# Ranger_PCB.net
KiCad netlist of a schematic drawn in EasyEDA
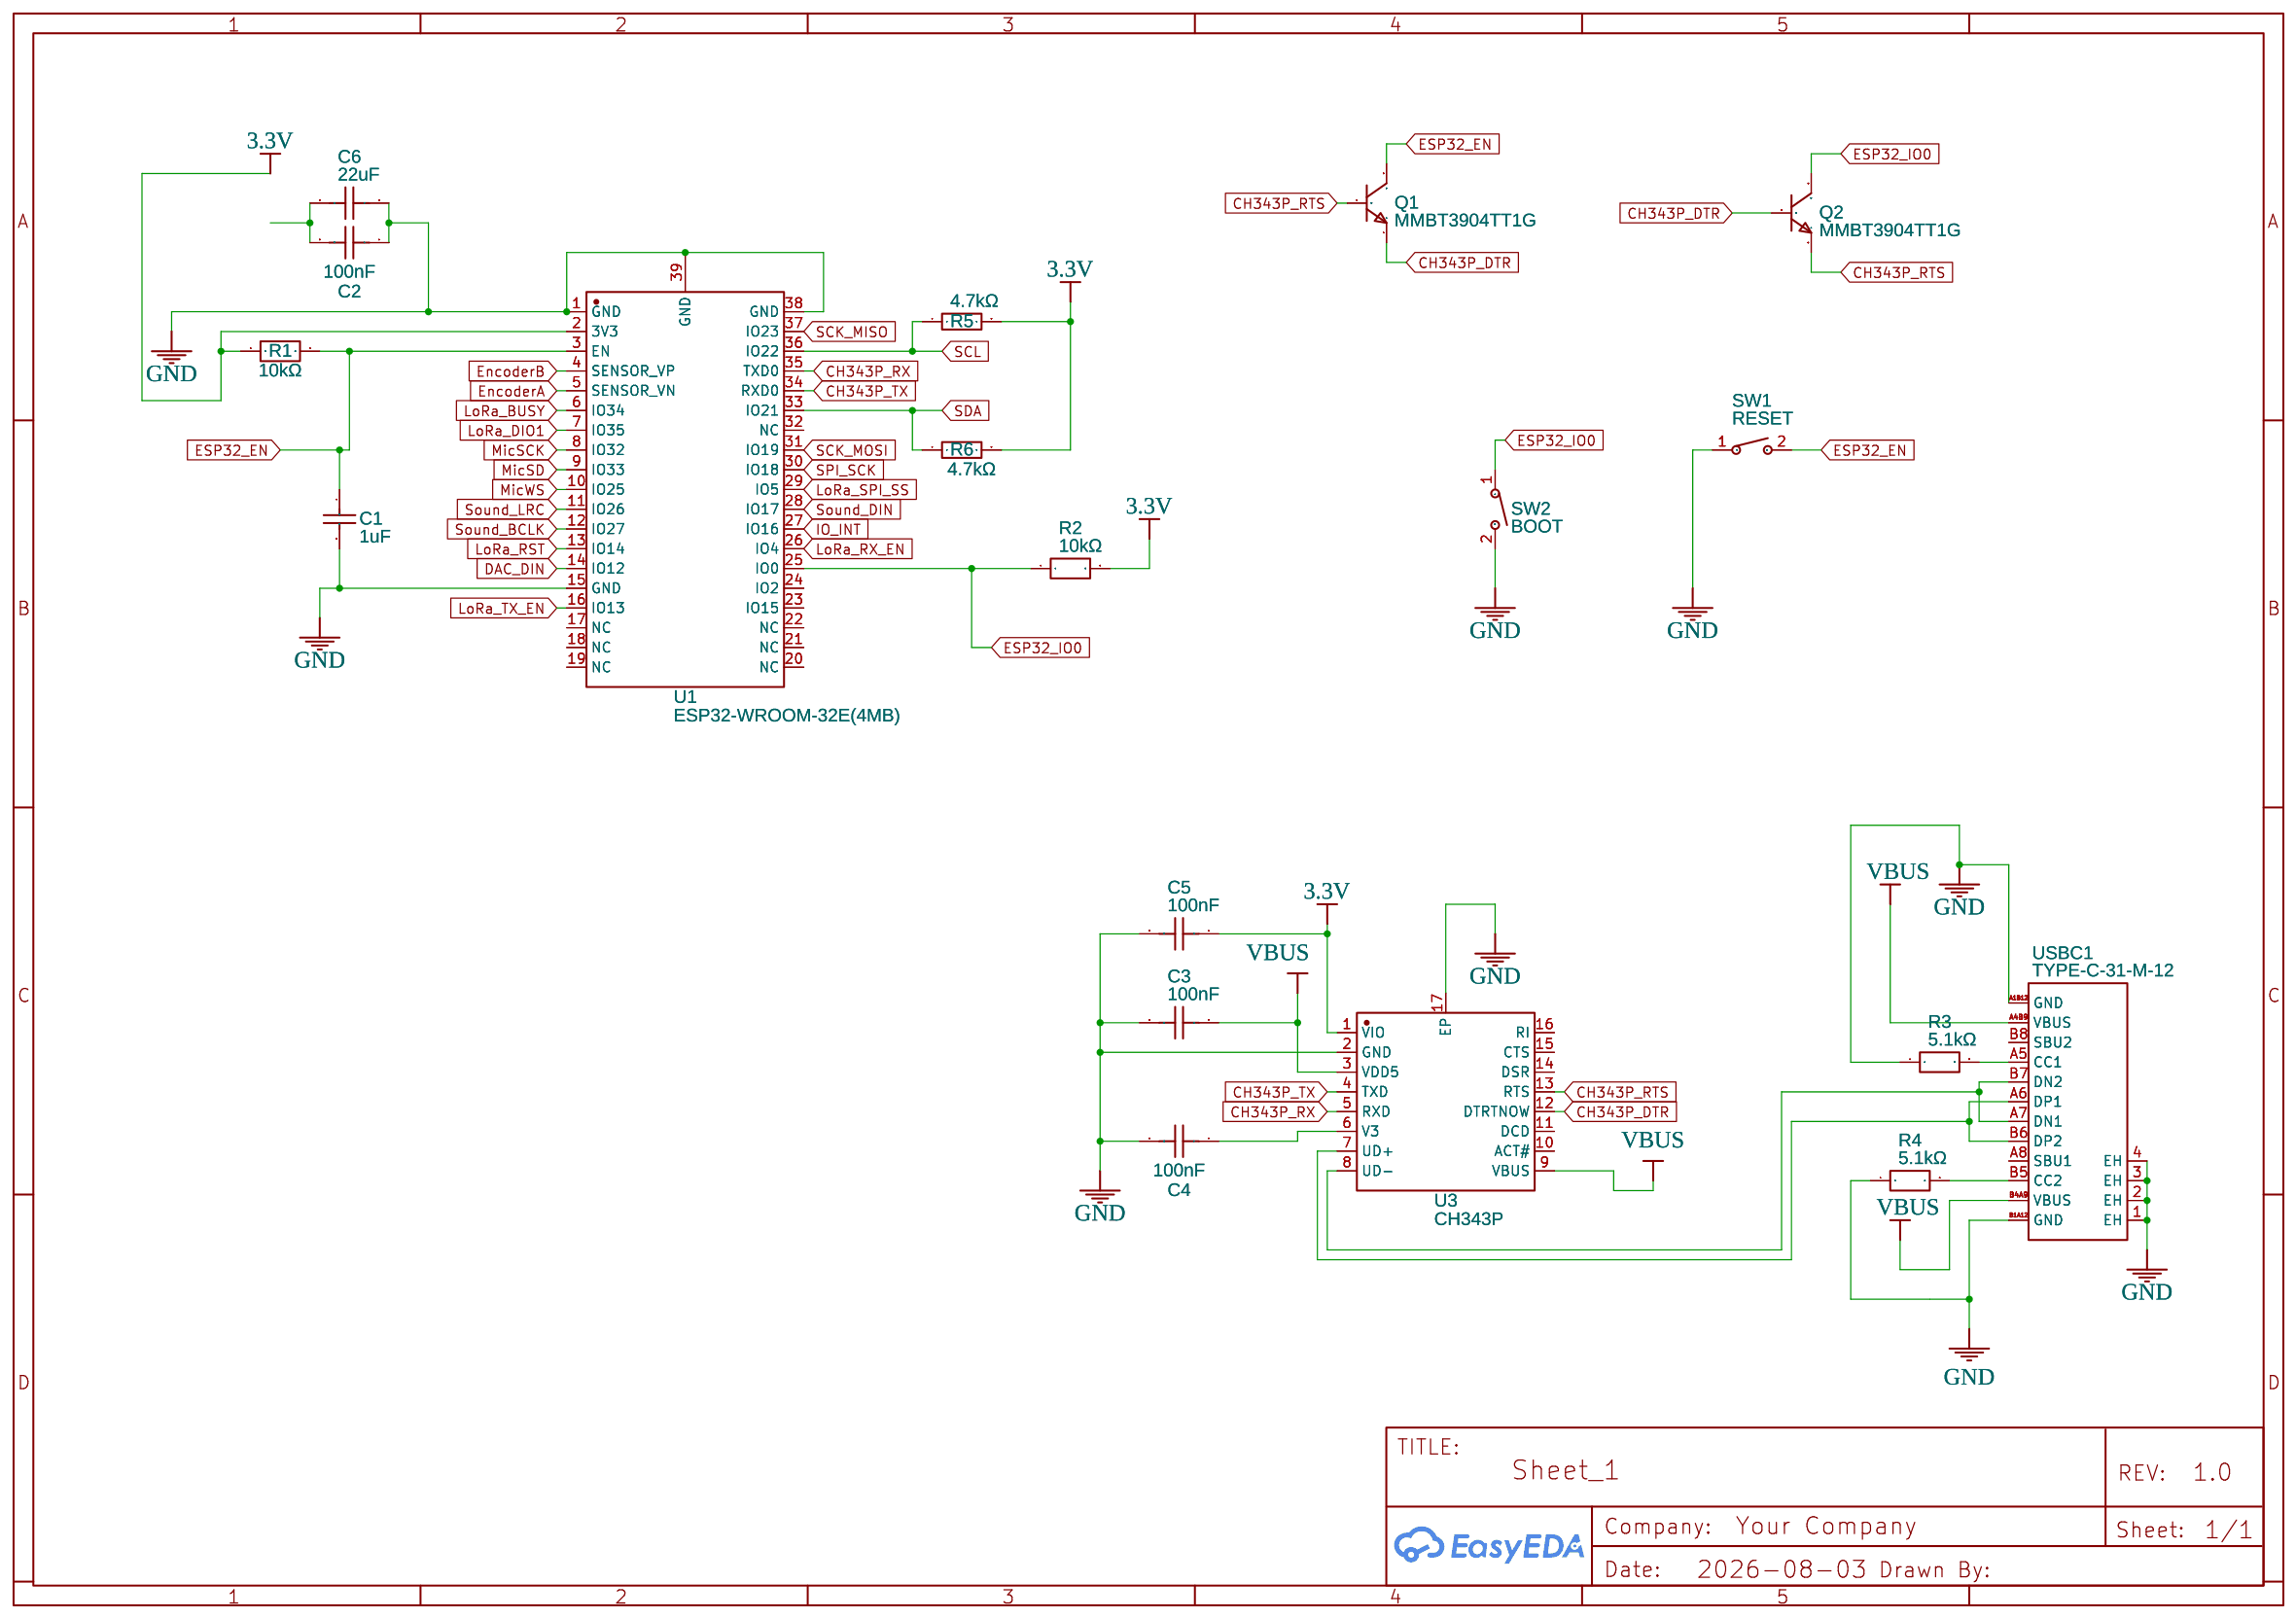
[diagram p0: ESP32]
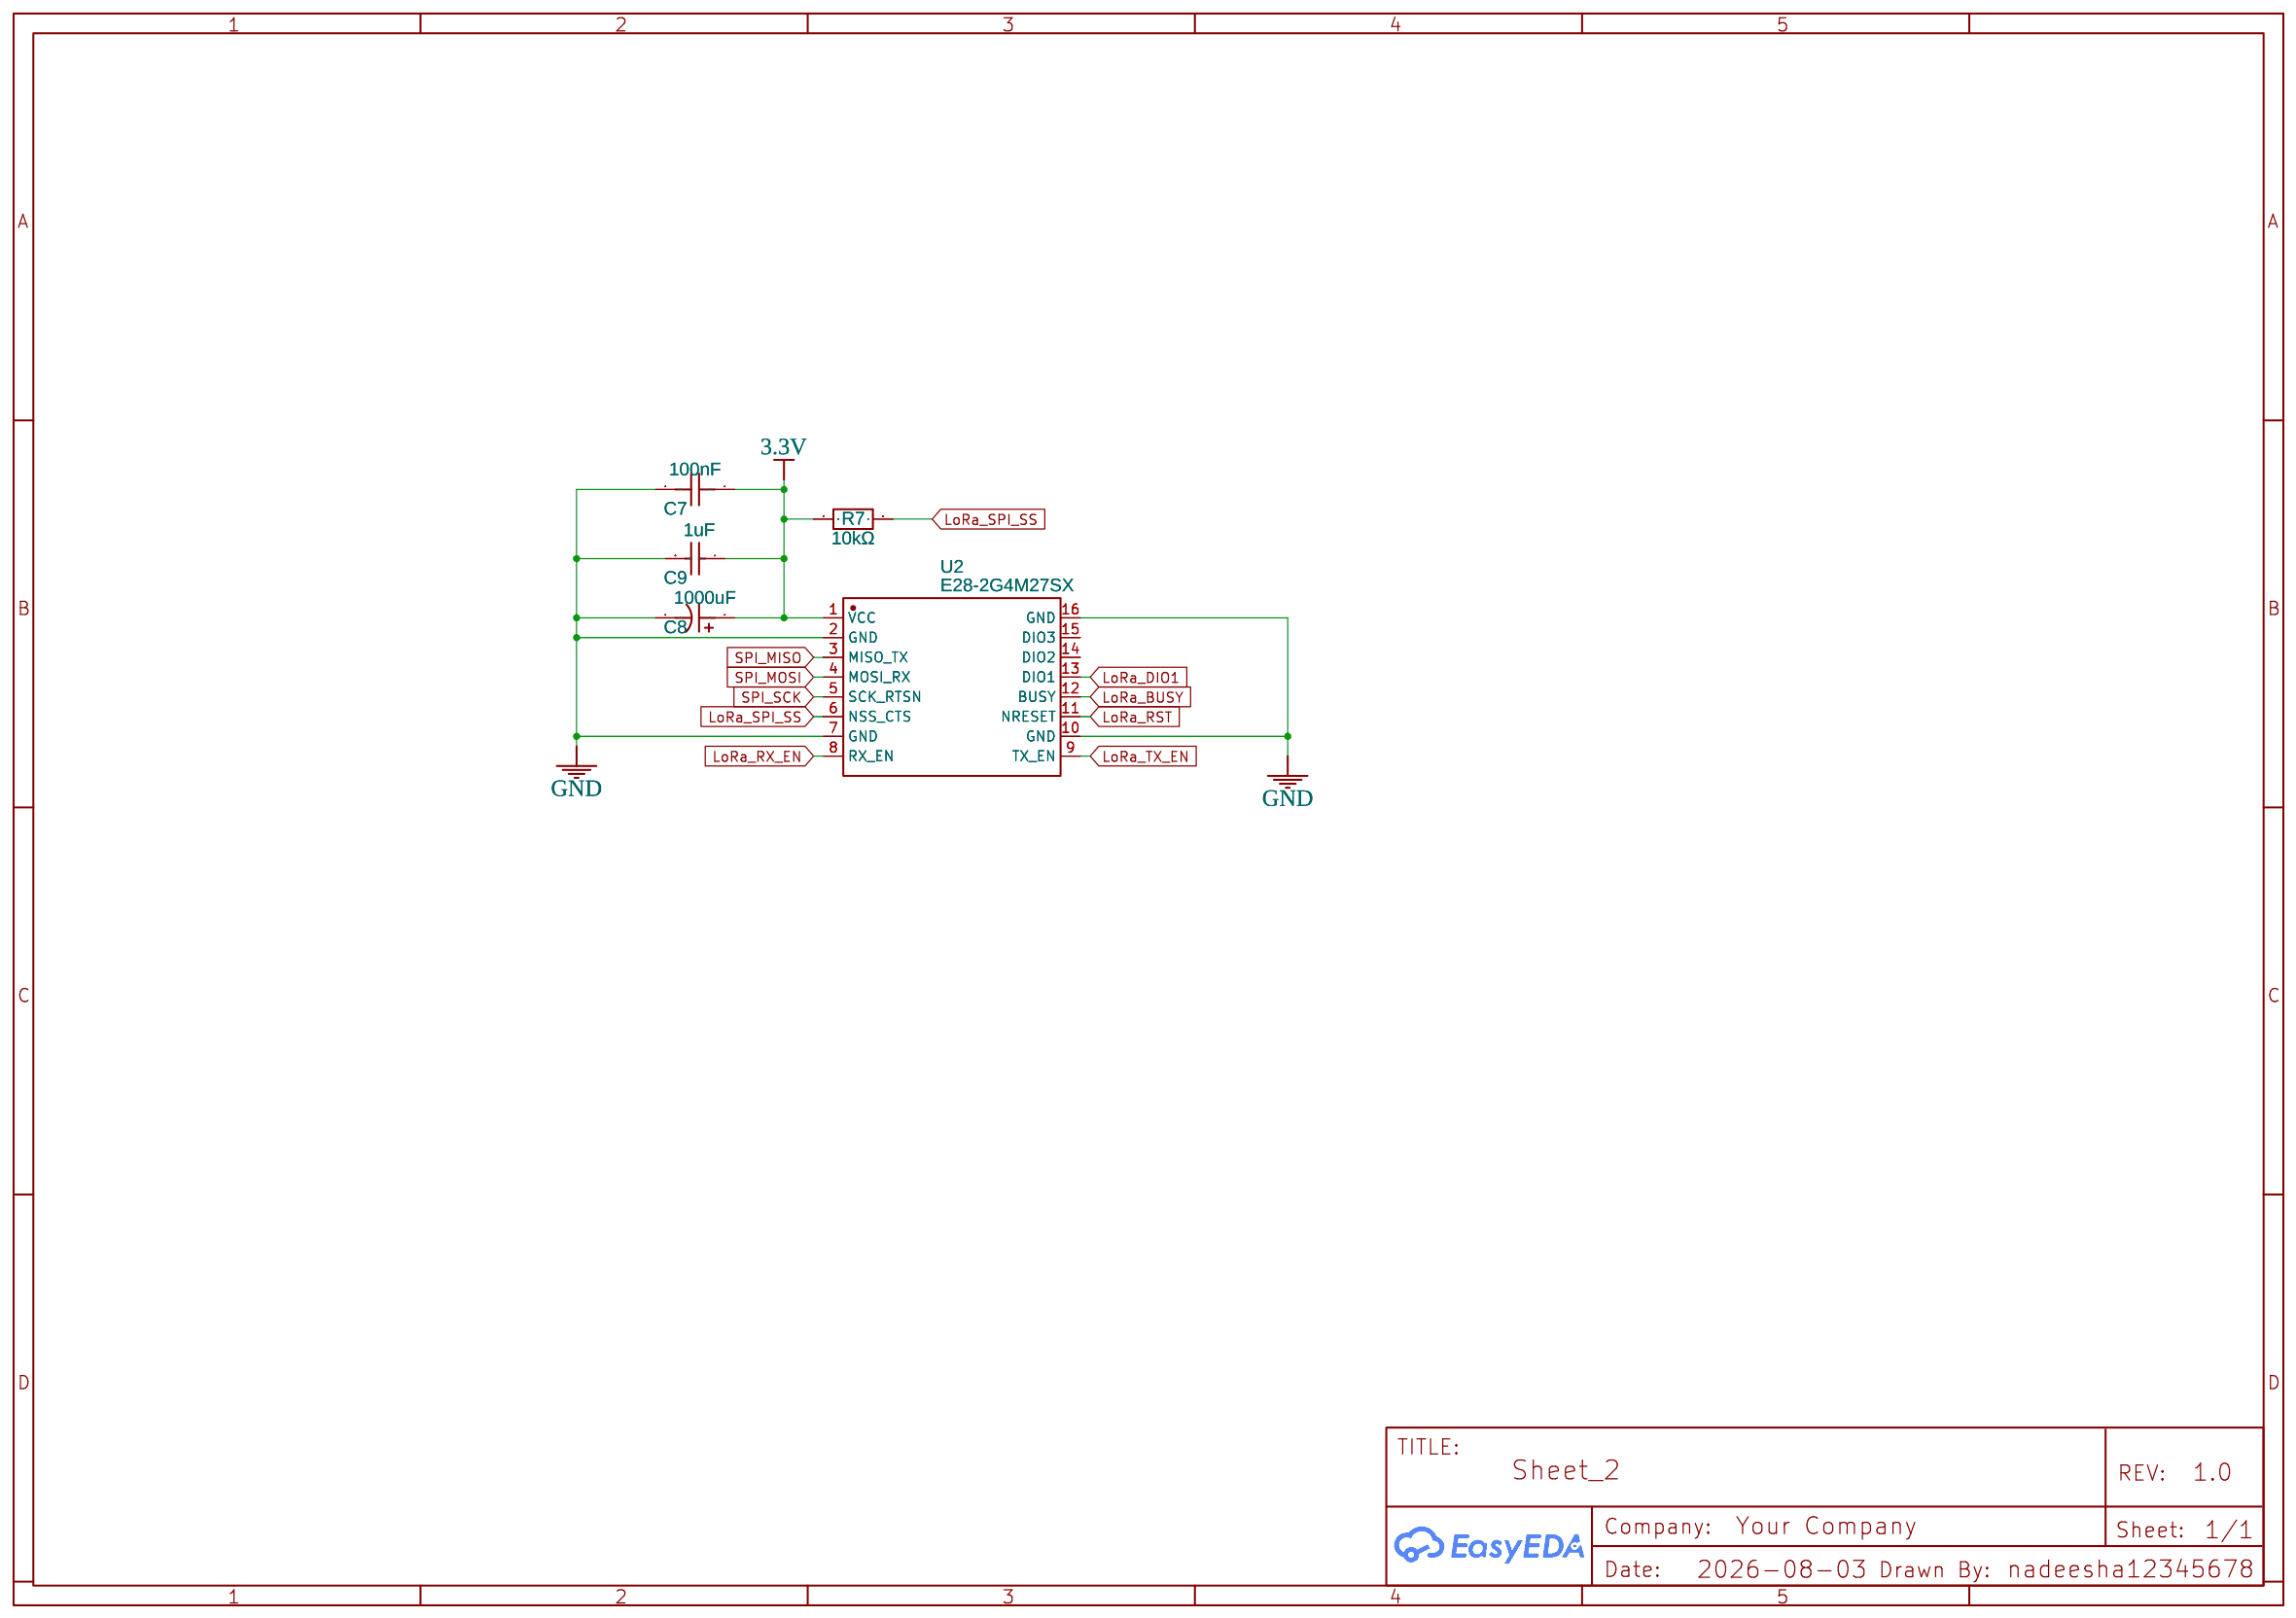
[diagram p1: LoRa]
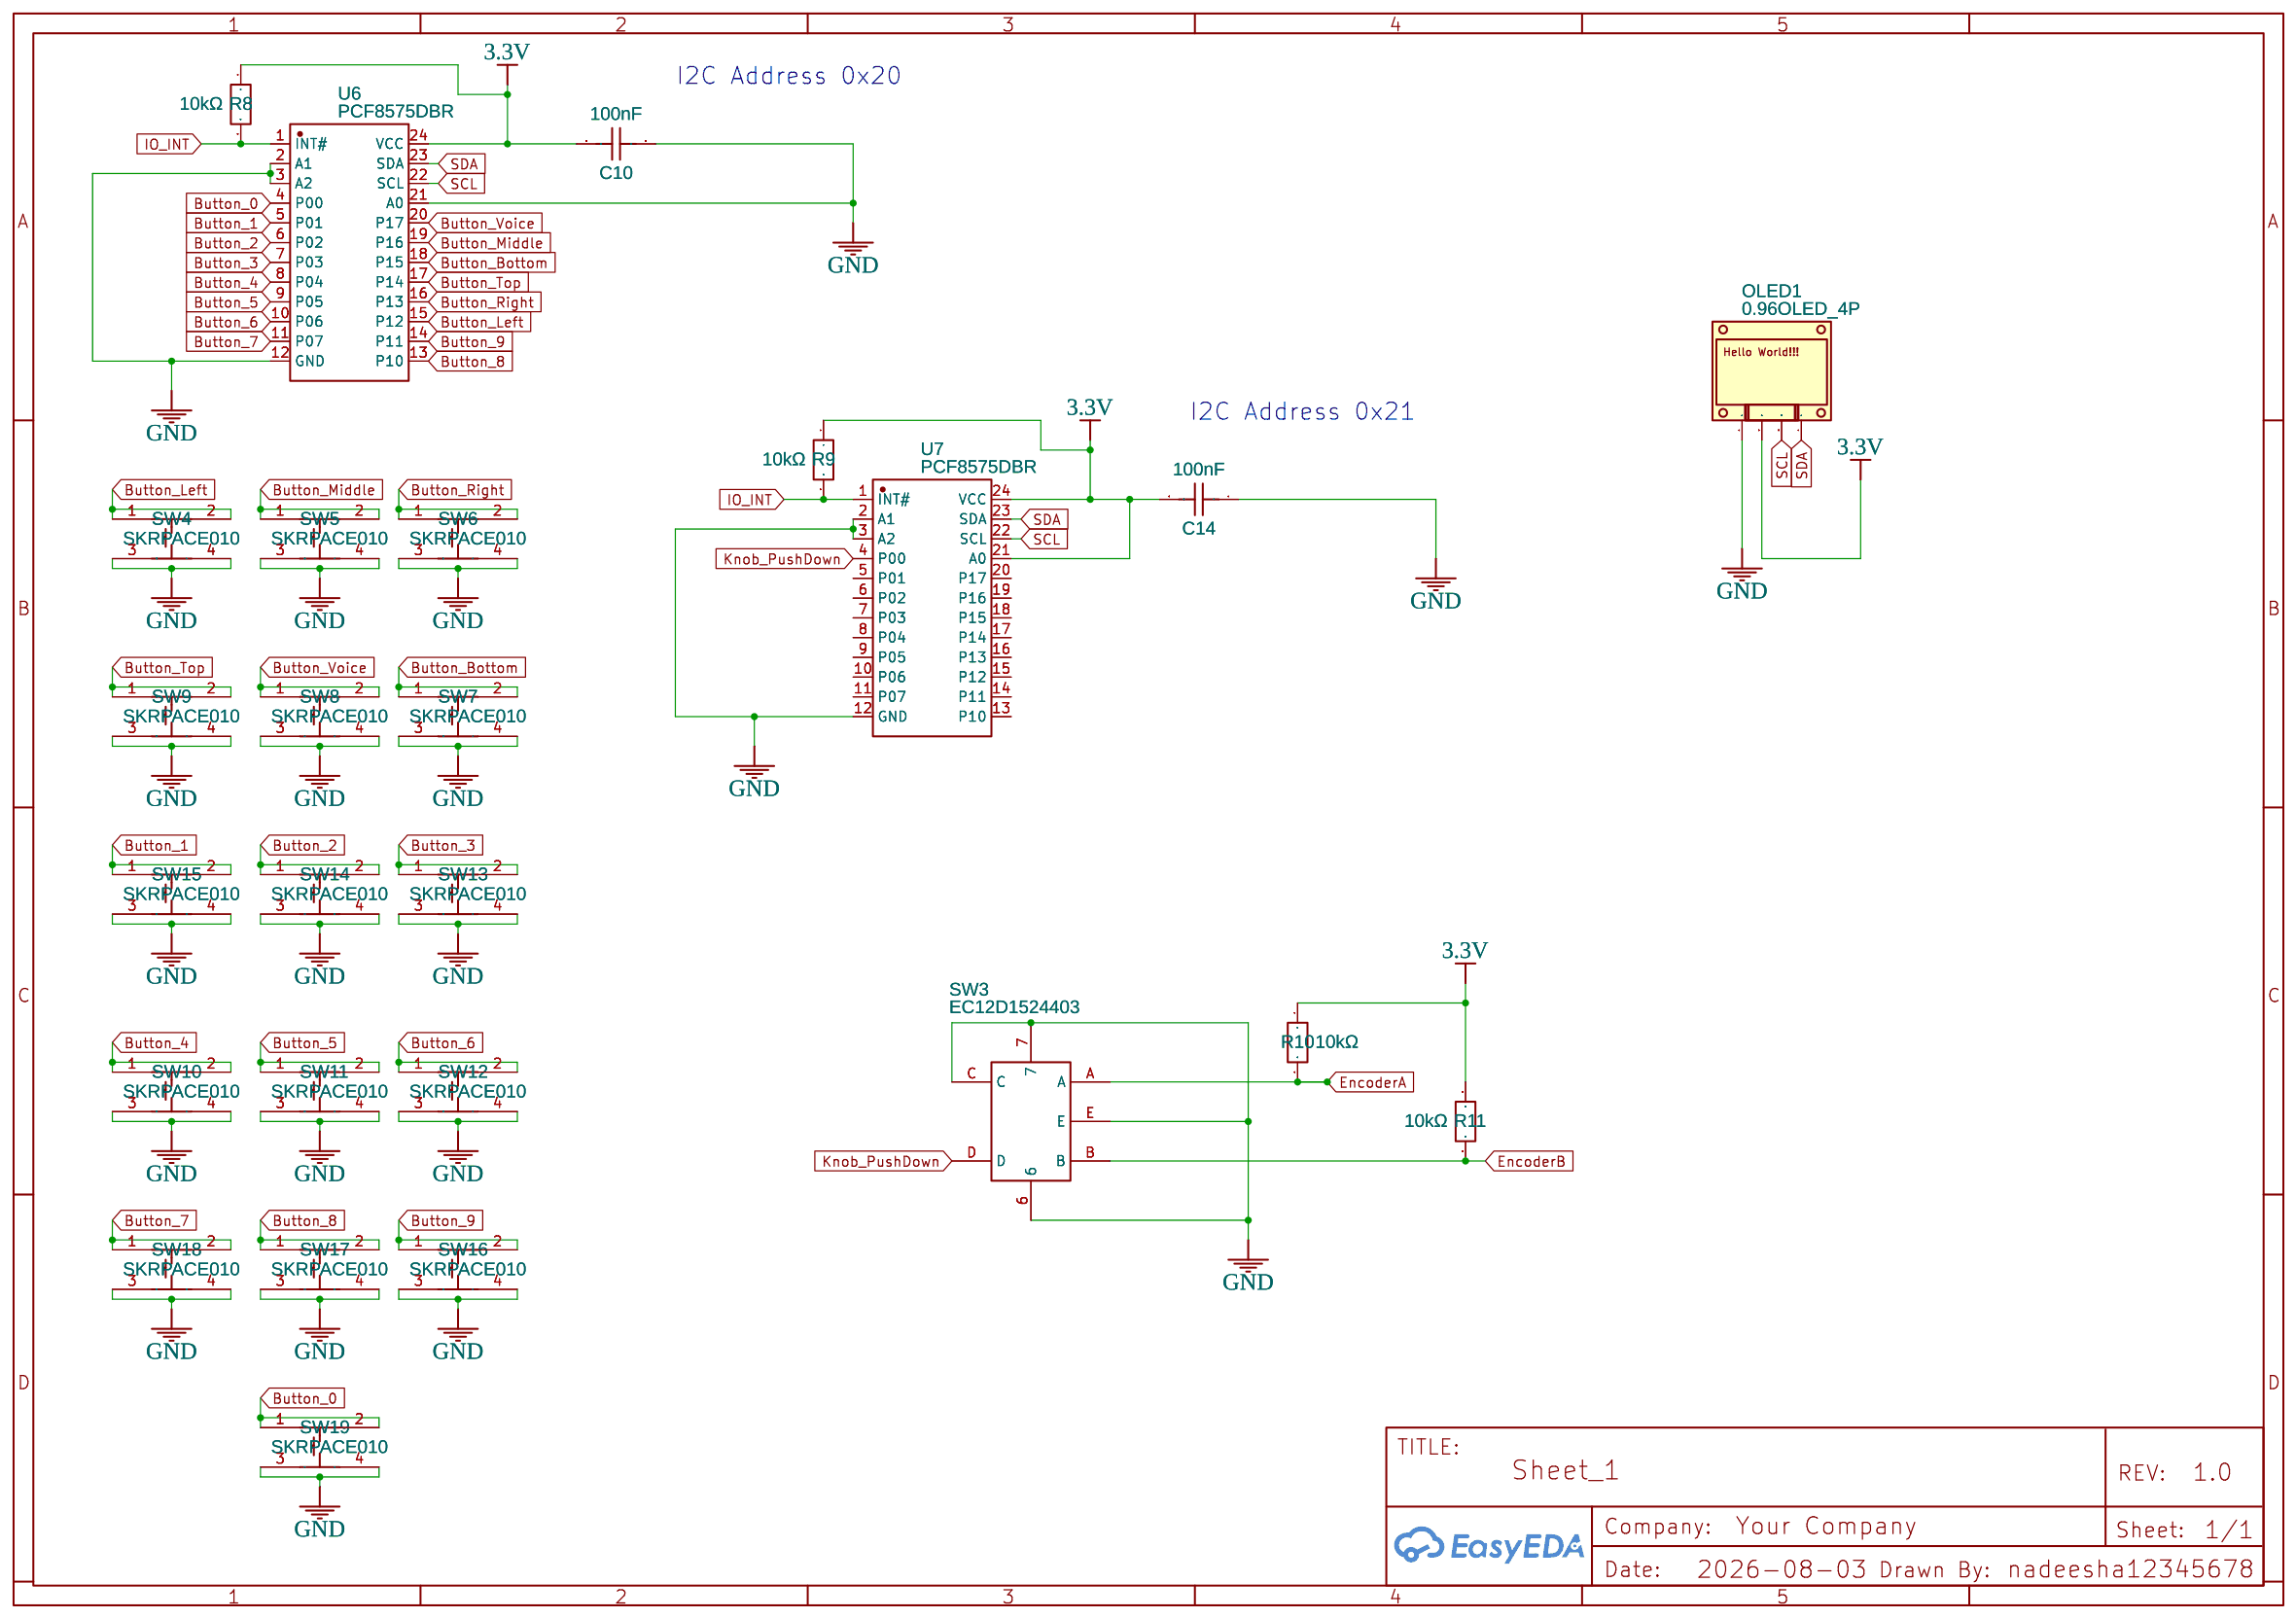
[diagram p2: Display, Buttons, LED]
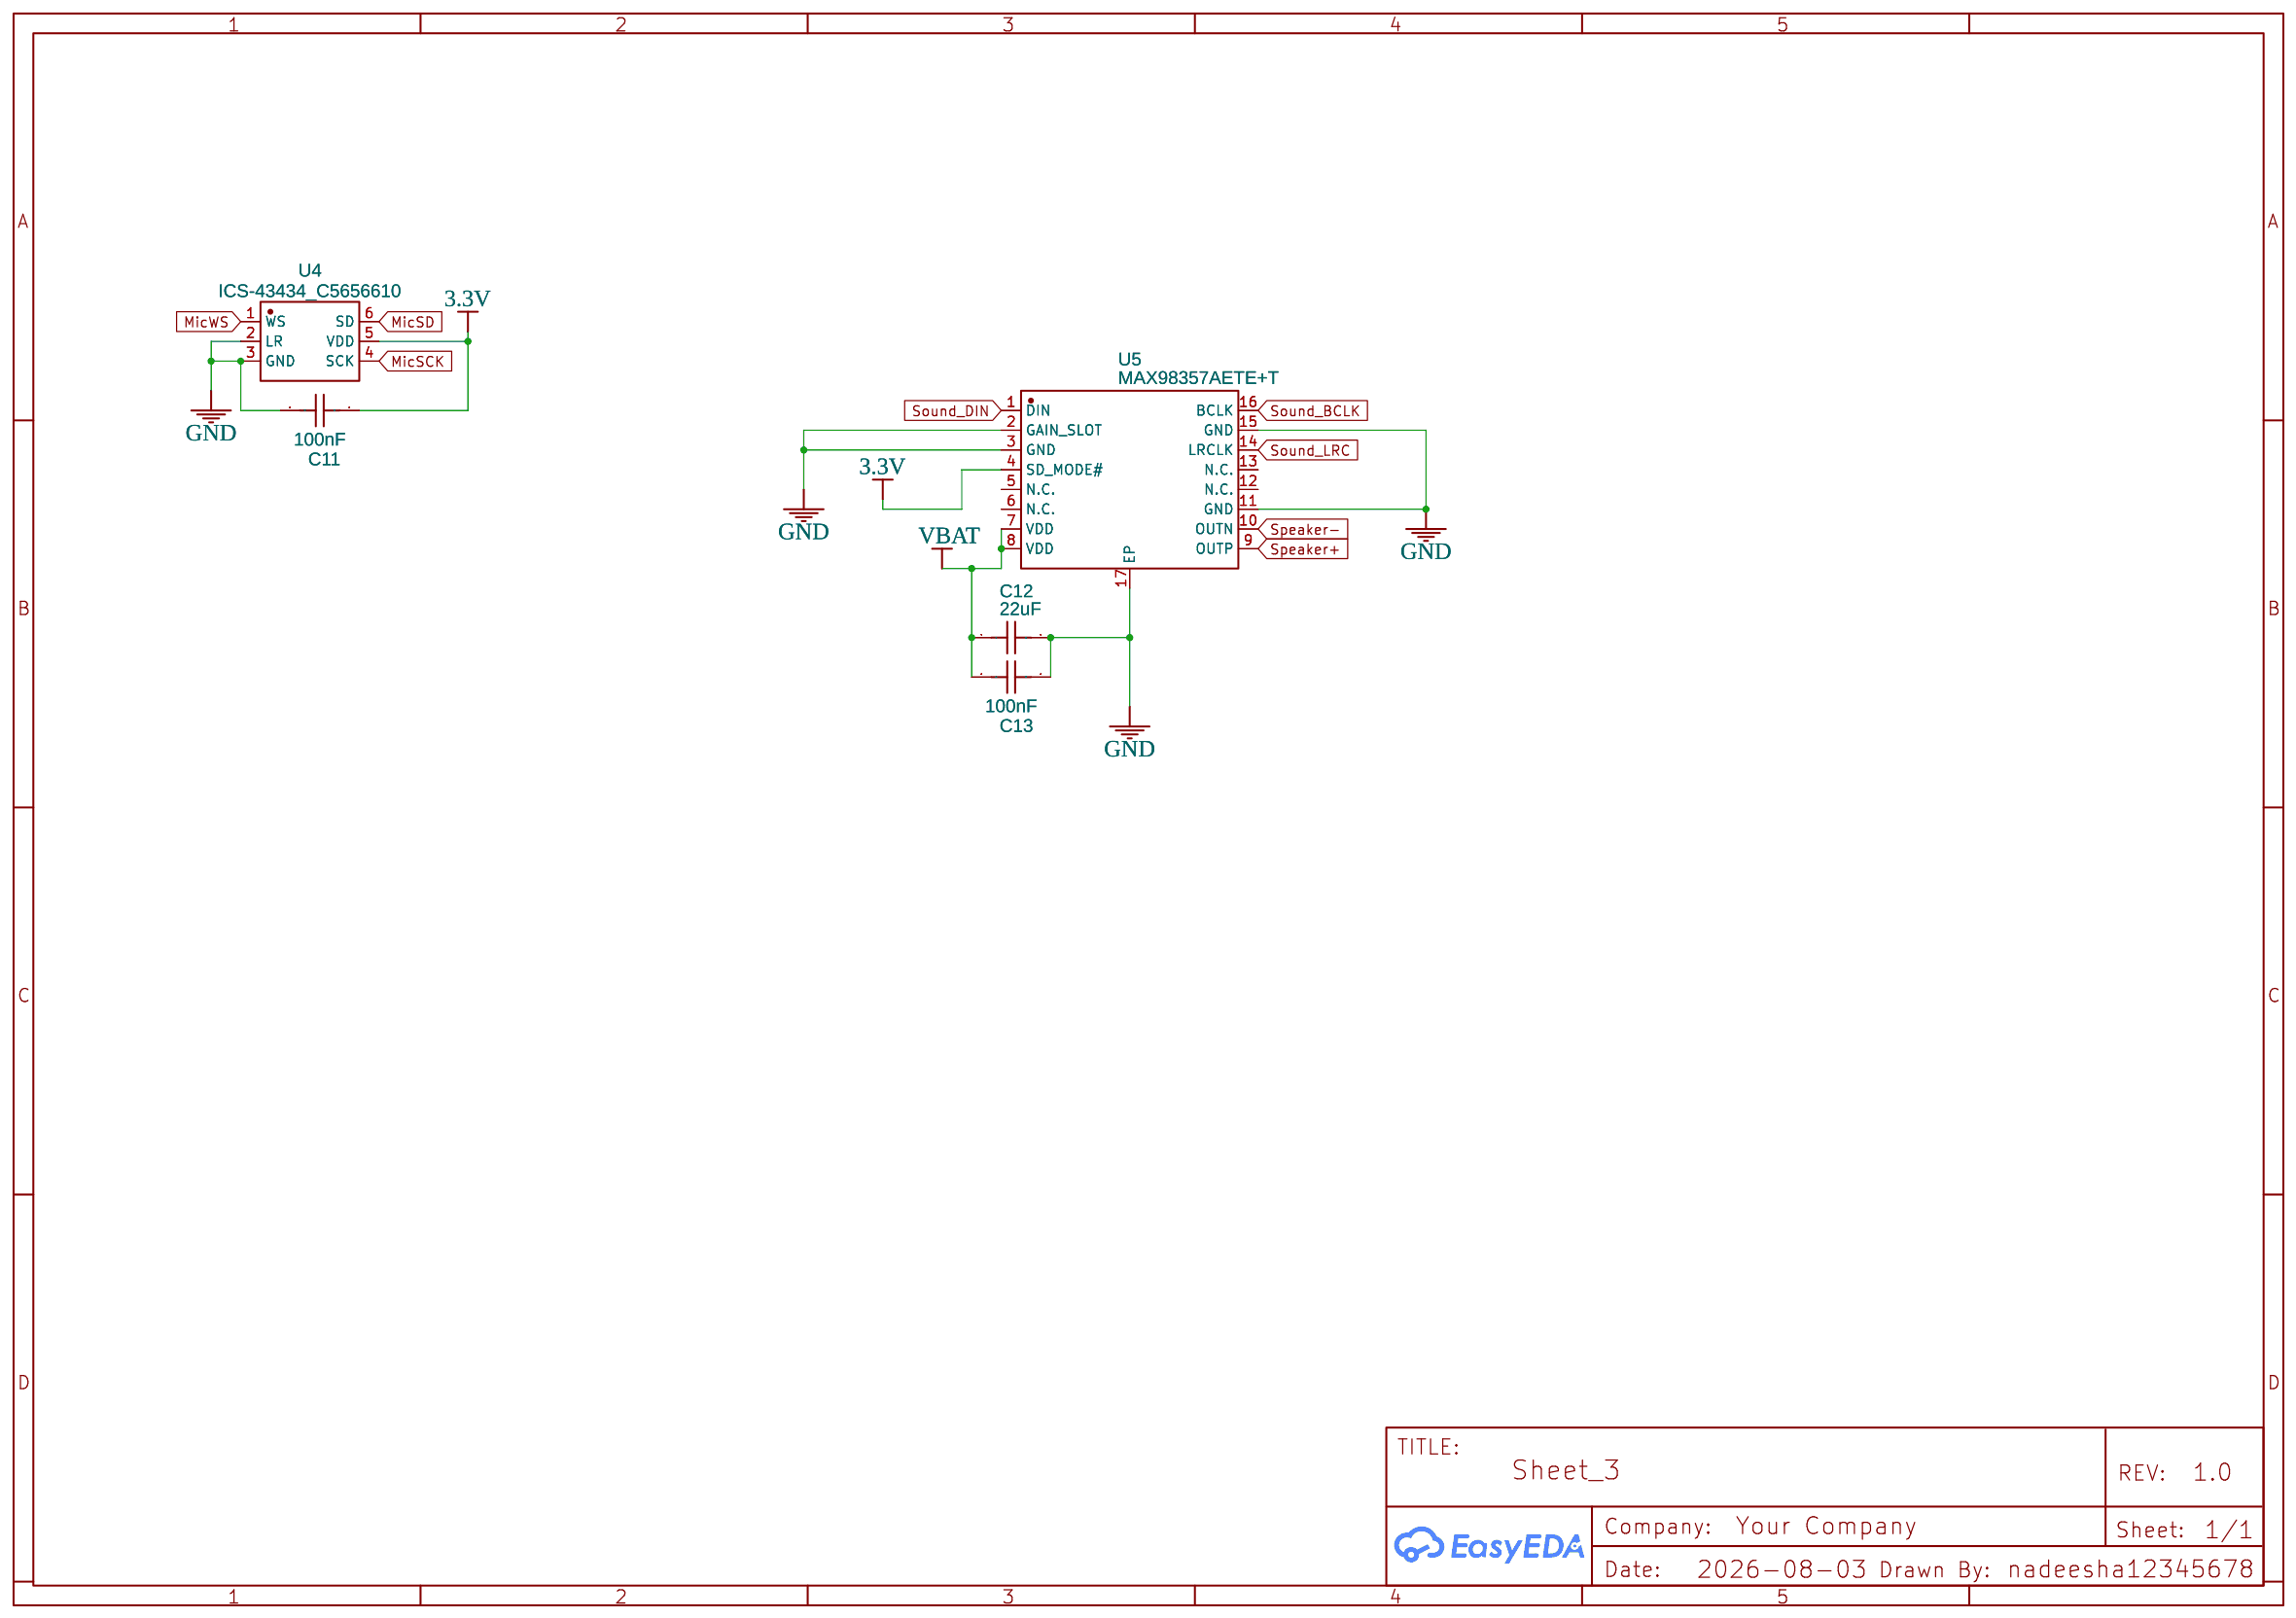
[diagram p3: Mic and Speaker]
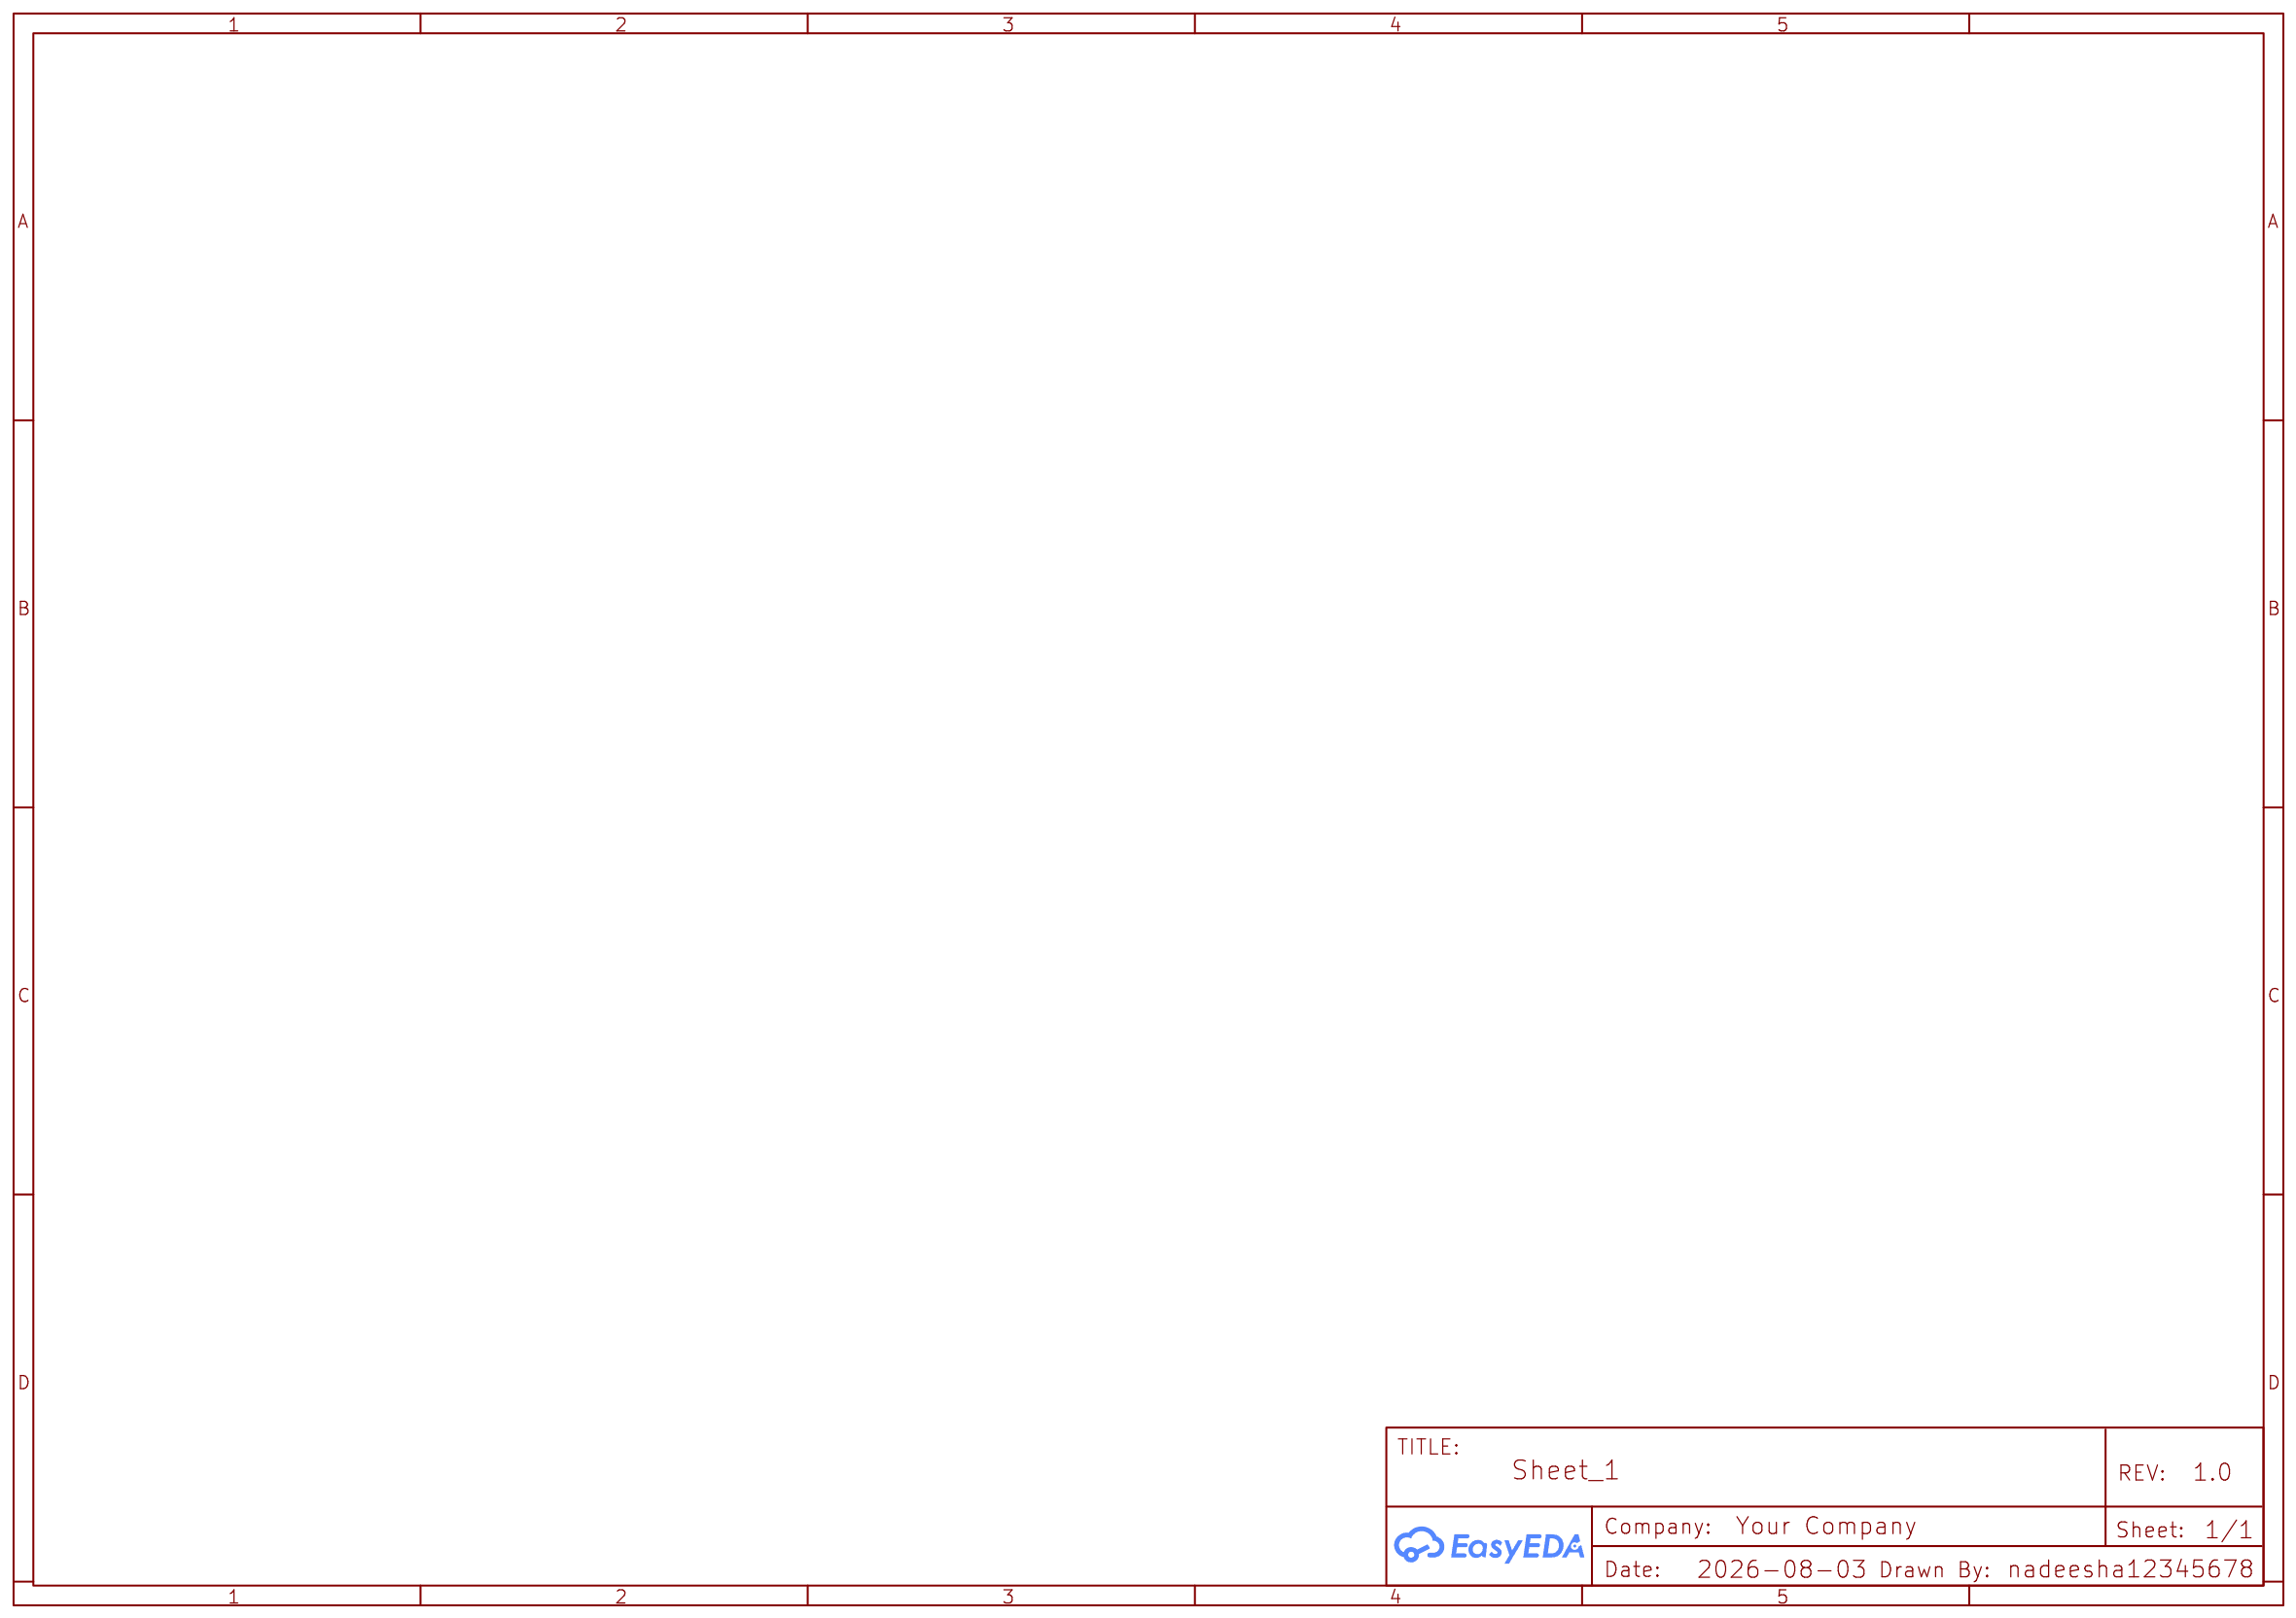
[diagram p4: Power]

(export (version "E")
  (design (tool "Eeschema 10.0.6"))
  (components
    (comp (ref "C1")
      (value "1uF")
      (fields
        (field (name "Manufacturer Part") "CL10B105KA8NNNC")
        (field (name "Manufacturer") "SAMSUNG(三星)")
      )
      (libsource (lib "") (part "CL10B105KA8NNNC"))
    )
    (comp (ref "C2")
      (value "100nF")
      (fields
        (field (name "Manufacturer Part") "CL10B104KB8NNNC")
        (field (name "Manufacturer") "SAMSUNG(三星)")
      )
      (libsource (lib "") (part "CL10B104KB8NNNC"))
    )
    (comp (ref "C3")
      (value "100nF")
      (fields
        (field (name "Manufacturer Part") "CL10B104KB8NNNC")
        (field (name "Manufacturer") "SAMSUNG(三星)")
      )
      (libsource (lib "") (part "CL10B104KB8NNNC"))
    )
    (comp (ref "C4")
      (value "100nF")
      (fields
        (field (name "Manufacturer Part") "CL10B104KB8NNNC")
        (field (name "Manufacturer") "SAMSUNG(三星)")
      )
      (libsource (lib "") (part "CL10B104KB8NNNC"))
    )
    (comp (ref "C5")
      (value "100nF")
      (fields
        (field (name "Manufacturer Part") "CL10B104KB8NNNC")
        (field (name "Manufacturer") "SAMSUNG(三星)")
      )
      (libsource (lib "") (part "CL10B104KB8NNNC"))
    )
    (comp (ref "C6")
      (value "22uF")
      (fields
        (field (name "Manufacturer Part") "CL10A226MP8NUNE")
        (field (name "Manufacturer") "SAMSUNG(三星)")
      )
      (libsource (lib "") (part "CL10A226MP8NUNE"))
    )
    (comp (ref "Q1")
      (value "MMBT3904TT1G")
      (fields (field (name "Manufacturer") "onsemi(安森美)"))
      (libsource (lib "") (part "MMBT3904TT1G"))
    )
    (comp (ref "Q2")
      (value "MMBT3904TT1G")
      (fields (field (name "Manufacturer") "onsemi(安森美)"))
      (libsource (lib "") (part "MMBT3904TT1G"))
    )
    (comp (ref "R1")
      (value "10kΩ")
      (fields (field (name "Manufacturer Part") "FRC0603F1002TS") (field (name "Manufacturer") "FOJAN(富捷)"))
      (libsource (lib "") (part "FRC0603F1002TS"))
    )
    (comp (ref "R2")
      (value "10kΩ")
      (fields (field (name "Manufacturer Part") "FRC0603F1002TS") (field (name "Manufacturer") "FOJAN(富捷)"))
      (libsource (lib "") (part "FRC0603F1002TS"))
    )
    (comp (ref "R3")
      (value "5.1kΩ")
      (fields (field (name "Manufacturer Part") "FRC0603F5101TS") (field (name "Manufacturer") "FOJAN(富捷)"))
      (libsource (lib "") (part "FRC0603F5101TS"))
    )
    (comp (ref "R4")
      (value "5.1kΩ")
      (fields (field (name "Manufacturer Part") "FRC0603F5101TS") (field (name "Manufacturer") "FOJAN(富捷)"))
      (libsource (lib "") (part "FRC0603F5101TS"))
    )
    (comp (ref "R5")
      (value "4.7kΩ")
      (fields (field (name "Manufacturer Part") "RC0603FR-074K7L") (field (name "Manufacturer") "YAGEO(国巨)"))
      (libsource (lib "") (part "RC0603FR-074K7L"))
    )
    (comp (ref "R6")
      (value "4.7kΩ")
      (fields (field (name "Manufacturer Part") "RC0603FR-074K7L") (field (name "Manufacturer") "YAGEO(国巨)"))
      (libsource (lib "") (part "RC0603FR-074K7L"))
    )
    (comp (ref "SW1")
      (value "RESET")
      (fields
        (field (name "Manufacturer Part") "HX 3x4x2-2P-1.6N TACTILE SWITCH")
        (field (name "Manufacturer") "hanxia(韩下)")
      )
      (libsource (lib "") (part "HX 3X4X2-2P-1.6N TACTILE SWITCH"))
    )
    (comp (ref "SW2")
      (value "BOOT")
      (fields
        (field (name "Manufacturer Part") "HX 3x4x2-2P-1.6N TACTILE SWITCH")
        (field (name "Manufacturer") "hanxia(韩下)")
      )
      (libsource (lib "") (part "HX 3X4X2-2P-1.6N TACTILE SWITCH_1"))
    )
    (comp (ref "U1")
      (value "ESP32-WROOM-32E(4MB)")
      (fields
        (field (name "Manufacturer Part") "ESP32-WROOM-32E-N4")
        (field (name "Manufacturer") "ESPRESSIF(乐鑫)")
      )
      (libsource (lib "") (part "ESP32-WROOM-32E(4MB)"))
    )
    (comp (ref "U3")
      (value "CH343P")
      (fields (field (name "Manufacturer") "WCH(南京沁恒)"))
      (libsource (lib "") (part "CH343P"))
    )
    (comp (ref "USBC1")
      (value "TYPE-C-31-M-12")
      (fields (field (name "Manufacturer") "韩国韩荣"))
      (libsource (lib "") (part "TYPE-C-31-M-12"))
    )
    (comp (ref "C7")
      (value "100nF")
      (fields
        (field (name "Manufacturer Part") "CL10B104KB8NNNC")
        (field (name "Manufacturer") "SAMSUNG(三星)")
      )
      (libsource (lib "") (part "CL10B104KB8NNNC"))
    )
    (comp (ref "C8")
      (value "1000uF")
      (fields (field (name "Manufacturer Part") "HV1A108M0810PZ") (field (name "Manufacturer") "HONOR(荣誉)"))
      (libsource (lib "") (part "HV1A108M0810PZ"))
    )
    (comp (ref "C9")
      (value "1uF")
      (fields
        (field (name "Manufacturer Part") "CL10B105KA8NNNC")
        (field (name "Manufacturer") "SAMSUNG(三星)")
      )
      (libsource (lib "") (part "CL10B105KA8NNNC"))
    )
    (comp (ref "R7")
      (value "10kΩ")
      (fields (field (name "Manufacturer Part") "FRC0603F1002TS") (field (name "Manufacturer") "FOJAN(富捷)"))
      (libsource (lib "") (part "FRC0603F1002TS"))
    )
    (comp (ref "U2")
      (value "E28-2G4M27SX")
      (fields (field (name "Manufacturer") "EBYTE(亿佰特)"))
      (libsource (lib "") (part "E28-2G4M27SX"))
    )
    (comp (ref "C10")
      (value "100nF")
      (fields
        (field (name "Manufacturer Part") "CL10B104KB8NNNC")
        (field (name "Manufacturer") "SAMSUNG(三星)")
      )
      (libsource (lib "") (part "CL10B104KB8NNNC"))
    )
    (comp (ref "C14")
      (value "100nF")
      (fields
        (field (name "Manufacturer Part") "CL10B104KB8NNNC")
        (field (name "Manufacturer") "SAMSUNG(三星)")
      )
      (libsource (lib "") (part "CL10B104KB8NNNC"))
    )
    (comp (ref "OLED1") (value "0.96OLED_4P") (libsource (lib "") (part "0.96OLED_4P")))
    (comp (ref "R8")
      (value "10kΩ")
      (fields (field (name "Manufacturer Part") "FRC0603F1002TS") (field (name "Manufacturer") "FOJAN(富捷)"))
      (libsource (lib "") (part "FRC0603F1002TS"))
    )
    (comp (ref "R9")
      (value "10kΩ")
      (fields (field (name "Manufacturer Part") "FRC0603F1002TS") (field (name "Manufacturer") "FOJAN(富捷)"))
      (libsource (lib "") (part "FRC0603F1002TS"))
    )
    (comp (ref "R10")
      (value "10kΩ")
      (fields (field (name "Manufacturer Part") "FRC0603F1002TS") (field (name "Manufacturer") "FOJAN(富捷)"))
      (libsource (lib "") (part "FRC0603F1002TS"))
    )
    (comp (ref "R11")
      (value "10kΩ")
      (fields (field (name "Manufacturer Part") "FRC0603F1002TS") (field (name "Manufacturer") "FOJAN(富捷)"))
      (libsource (lib "") (part "FRC0603F1002TS"))
    )
    (comp (ref "SW3")
      (value "EC12D1524403")
      (fields (field (name "Manufacturer") "ALPSALPINE(阿尔卑斯阿尔派)"))
      (libsource (lib "") (part "EC12D1524403"))
    )
    (comp (ref "SW4")
      (value "SKRPACE010")
      (fields (field (name "Manufacturer") "ALPSALPINE(阿尔卑斯阿尔派)"))
      (libsource (lib "") (part "SKRPACE010"))
    )
    (comp (ref "SW5")
      (value "SKRPACE010")
      (fields (field (name "Manufacturer") "ALPSALPINE(阿尔卑斯阿尔派)"))
      (libsource (lib "") (part "SKRPACE010"))
    )
    (comp (ref "SW6")
      (value "SKRPACE010")
      (fields (field (name "Manufacturer") "ALPSALPINE(阿尔卑斯阿尔派)"))
      (libsource (lib "") (part "SKRPACE010"))
    )
    (comp (ref "SW7")
      (value "SKRPACE010")
      (fields (field (name "Manufacturer") "ALPSALPINE(阿尔卑斯阿尔派)"))
      (libsource (lib "") (part "SKRPACE010"))
    )
    (comp (ref "SW8")
      (value "SKRPACE010")
      (fields (field (name "Manufacturer") "ALPSALPINE(阿尔卑斯阿尔派)"))
      (libsource (lib "") (part "SKRPACE010"))
    )
    (comp (ref "SW9")
      (value "SKRPACE010")
      (fields (field (name "Manufacturer") "ALPSALPINE(阿尔卑斯阿尔派)"))
      (libsource (lib "") (part "SKRPACE010"))
    )
    (comp (ref "SW10")
      (value "SKRPACE010")
      (fields (field (name "Manufacturer") "ALPSALPINE(阿尔卑斯阿尔派)"))
      (libsource (lib "") (part "SKRPACE010"))
    )
    (comp (ref "SW11")
      (value "SKRPACE010")
      (fields (field (name "Manufacturer") "ALPSALPINE(阿尔卑斯阿尔派)"))
      (libsource (lib "") (part "SKRPACE010"))
    )
    (comp (ref "SW12")
      (value "SKRPACE010")
      (fields (field (name "Manufacturer") "ALPSALPINE(阿尔卑斯阿尔派)"))
      (libsource (lib "") (part "SKRPACE010"))
    )
    (comp (ref "SW13")
      (value "SKRPACE010")
      (fields (field (name "Manufacturer") "ALPSALPINE(阿尔卑斯阿尔派)"))
      (libsource (lib "") (part "SKRPACE010"))
    )
    (comp (ref "SW14")
      (value "SKRPACE010")
      (fields (field (name "Manufacturer") "ALPSALPINE(阿尔卑斯阿尔派)"))
      (libsource (lib "") (part "SKRPACE010"))
    )
    (comp (ref "SW15")
      (value "SKRPACE010")
      (fields (field (name "Manufacturer") "ALPSALPINE(阿尔卑斯阿尔派)"))
      (libsource (lib "") (part "SKRPACE010"))
    )
    (comp (ref "SW16")
      (value "SKRPACE010")
      (fields (field (name "Manufacturer") "ALPSALPINE(阿尔卑斯阿尔派)"))
      (libsource (lib "") (part "SKRPACE010"))
    )
    (comp (ref "SW17")
      (value "SKRPACE010")
      (fields (field (name "Manufacturer") "ALPSALPINE(阿尔卑斯阿尔派)"))
      (libsource (lib "") (part "SKRPACE010"))
    )
    (comp (ref "SW18")
      (value "SKRPACE010")
      (fields (field (name "Manufacturer") "ALPSALPINE(阿尔卑斯阿尔派)"))
      (libsource (lib "") (part "SKRPACE010"))
    )
    (comp (ref "SW19")
      (value "SKRPACE010")
      (fields (field (name "Manufacturer") "ALPSALPINE(阿尔卑斯阿尔派)"))
      (libsource (lib "") (part "SKRPACE010"))
    )
    (comp (ref "U6")
      (value "PCF8575DBR")
      (fields (field (name "Manufacturer") "TI(德州仪器)"))
      (libsource (lib "") (part "PCF8575DBR"))
    )
    (comp (ref "U7")
      (value "PCF8575DBR")
      (fields (field (name "Manufacturer") "TI(德州仪器)"))
      (libsource (lib "") (part "PCF8575DBR"))
    )
    (comp (ref "C11")
      (value "100nF")
      (fields
        (field (name "Manufacturer Part") "CL10B104KB8NNNC")
        (field (name "Manufacturer") "SAMSUNG(三星)")
      )
      (libsource (lib "") (part "CL10B104KB8NNNC"))
    )
    (comp (ref "C12")
      (value "22uF")
      (fields
        (field (name "Manufacturer Part") "CL10A226MP8NUNE")
        (field (name "Manufacturer") "SAMSUNG(三星)")
      )
      (libsource (lib "") (part "CL10A226MP8NUNE"))
    )
    (comp (ref "C13")
      (value "100nF")
      (fields
        (field (name "Manufacturer Part") "CL10B104KB8NNNC")
        (field (name "Manufacturer") "SAMSUNG(三星)")
      )
      (libsource (lib "") (part "CL10B104KB8NNNC"))
    )
    (comp (ref "U4")
      (value "ICS-43434_C5656610")
      (fields
        (field (name "Manufacturer Part") "ICS-43434")
        (field (name "Manufacturer") "TDK InvenSense(应美盛)")
      )
      (libsource (lib "") (part "ICS-43434_C5656610"))
    )
    (comp (ref "U5")
      (value "MAX98357AETE+T")
      (fields (field (name "Manufacturer") "ADI(亚德诺)/MAXIM(美信)"))
      (libsource (lib "") (part "MAX98357AETE+T"))
    )
  )
  (nets
    (net (code "1") (name "3.3V") (class "Default")
      (node (ref "C10") (pin "2") (pinfunction "2_2") (pintype "unspecified"))
      (node (ref "C11") (pin "1") (pinfunction "1_1") (pintype "unspecified"))
      (node (ref "C14") (pin "2") (pinfunction "2_2") (pintype "unspecified"))
      (node (ref "C5") (pin "1") (pinfunction "1_1") (pintype "unspecified"))
      (node (ref "C7") (pin "1") (pinfunction "1_1") (pintype "unspecified"))
      (node (ref "C8") (pin "1") (pinfunction "1_1") (pintype "input"))
      (node (ref "C9") (pin "1") (pinfunction "1_1") (pintype "input"))
      (node (ref "OLED1") (pin "2") (pinfunction "2_2") (pintype "unspecified"))
      (node (ref "R1") (pin "1") (pinfunction "1_1") (pintype "unspecified"))
      (node (ref "R10") (pin "1") (pinfunction "1_1") (pintype "unspecified"))
      (node (ref "R11") (pin "1") (pinfunction "1_1") (pintype "unspecified"))
      (node (ref "R2") (pin "2") (pinfunction "2_2") (pintype "unspecified"))
      (node (ref "R5") (pin "2") (pinfunction "2_2") (pintype "input"))
      (node (ref "R6") (pin "2") (pinfunction "2_2") (pintype "input"))
      (node (ref "R7") (pin "1") (pinfunction "1_1") (pintype "unspecified"))
      (node (ref "R8") (pin "1") (pinfunction "1_1") (pintype "unspecified"))
      (node (ref "R9") (pin "1") (pinfunction "1_1") (pintype "unspecified"))
      (node (ref "U1") (pin "2") (pinfunction "3V3_2") (pintype "unspecified"))
      (node (ref "U2") (pin "1") (pinfunction "VCC_1") (pintype "unspecified"))
      (node (ref "U3") (pin "1") (pinfunction "VIO_1") (pintype "unspecified"))
      (node (ref "U4") (pin "5") (pinfunction "VDD_5") (pintype "unspecified"))
      (node (ref "U5") (pin "4") (pinfunction "SD_MODE#_4") (pintype "unspecified"))
      (node (ref "U6") (pin "24") (pinfunction "VCC_24") (pintype "unspecified"))
      (node (ref "U7") (pin "21") (pinfunction "A0_21") (pintype "unspecified"))
      (node (ref "U7") (pin "24") (pinfunction "VCC_24") (pintype "unspecified"))
    )
    (net (code "2") (name "Button_0") (class "Default")
      (node (ref "SW19") (pin "1") (pinfunction "1_1") (pintype "unspecified"))
      (node (ref "SW19") (pin "2") (pinfunction "2_2") (pintype "unspecified"))
      (node (ref "U6") (pin "4") (pinfunction "P00_4") (pintype "unspecified"))
    )
    (net (code "3") (name "Button_1") (class "Default")
      (node (ref "SW15") (pin "1") (pinfunction "1_1") (pintype "unspecified"))
      (node (ref "SW15") (pin "2") (pinfunction "2_2") (pintype "unspecified"))
      (node (ref "U6") (pin "5") (pinfunction "P01_5") (pintype "unspecified"))
    )
    (net (code "4") (name "Button_2") (class "Default")
      (node (ref "SW14") (pin "1") (pinfunction "1_1") (pintype "unspecified"))
      (node (ref "SW14") (pin "2") (pinfunction "2_2") (pintype "unspecified"))
      (node (ref "U6") (pin "6") (pinfunction "P02_6") (pintype "unspecified"))
    )
    (net (code "5") (name "Button_3") (class "Default")
      (node (ref "SW13") (pin "1") (pinfunction "1_1") (pintype "unspecified"))
      (node (ref "SW13") (pin "2") (pinfunction "2_2") (pintype "unspecified"))
      (node (ref "U6") (pin "7") (pinfunction "P03_7") (pintype "unspecified"))
    )
    (net (code "6") (name "Button_4") (class "Default")
      (node (ref "SW10") (pin "1") (pinfunction "1_1") (pintype "unspecified"))
      (node (ref "SW10") (pin "2") (pinfunction "2_2") (pintype "unspecified"))
      (node (ref "U6") (pin "8") (pinfunction "P04_8") (pintype "unspecified"))
    )
    (net (code "7") (name "Button_5") (class "Default")
      (node (ref "SW11") (pin "1") (pinfunction "1_1") (pintype "unspecified"))
      (node (ref "SW11") (pin "2") (pinfunction "2_2") (pintype "unspecified"))
      (node (ref "U6") (pin "9") (pinfunction "P05_9") (pintype "unspecified"))
    )
    (net (code "8") (name "Button_6") (class "Default")
      (node (ref "SW12") (pin "1") (pinfunction "1_1") (pintype "unspecified"))
      (node (ref "SW12") (pin "2") (pinfunction "2_2") (pintype "unspecified"))
      (node (ref "U6") (pin "10") (pinfunction "P06_10") (pintype "unspecified"))
    )
    (net (code "9") (name "Button_7") (class "Default")
      (node (ref "SW18") (pin "1") (pinfunction "1_1") (pintype "unspecified"))
      (node (ref "SW18") (pin "2") (pinfunction "2_2") (pintype "unspecified"))
      (node (ref "U6") (pin "11") (pinfunction "P07_11") (pintype "unspecified"))
    )
    (net (code "10") (name "Button_8") (class "Default")
      (node (ref "SW17") (pin "1") (pinfunction "1_1") (pintype "unspecified"))
      (node (ref "SW17") (pin "2") (pinfunction "2_2") (pintype "unspecified"))
      (node (ref "U6") (pin "13") (pinfunction "P10_13") (pintype "unspecified"))
    )
    (net (code "11") (name "Button_9") (class "Default")
      (node (ref "SW16") (pin "1") (pinfunction "1_1") (pintype "unspecified"))
      (node (ref "SW16") (pin "2") (pinfunction "2_2") (pintype "unspecified"))
      (node (ref "U6") (pin "14") (pinfunction "P11_14") (pintype "unspecified"))
    )
    (net (code "12") (name "Button_Bottom") (class "Default")
      (node (ref "SW7") (pin "1") (pinfunction "1_1") (pintype "unspecified"))
      (node (ref "SW7") (pin "2") (pinfunction "2_2") (pintype "unspecified"))
      (node (ref "U6") (pin "18") (pinfunction "P15_18") (pintype "unspecified"))
    )
    (net (code "13") (name "Button_Left") (class "Default")
      (node (ref "SW4") (pin "1") (pinfunction "1_1") (pintype "unspecified"))
      (node (ref "SW4") (pin "2") (pinfunction "2_2") (pintype "unspecified"))
      (node (ref "U6") (pin "15") (pinfunction "P12_15") (pintype "unspecified"))
    )
    (net (code "14") (name "Button_Middle") (class "Default")
      (node (ref "SW5") (pin "1") (pinfunction "1_1") (pintype "unspecified"))
      (node (ref "SW5") (pin "2") (pinfunction "2_2") (pintype "unspecified"))
      (node (ref "U6") (pin "19") (pinfunction "P16_19") (pintype "unspecified"))
    )
    (net (code "15") (name "Button_Right") (class "Default")
      (node (ref "SW6") (pin "1") (pinfunction "1_1") (pintype "unspecified"))
      (node (ref "SW6") (pin "2") (pinfunction "2_2") (pintype "unspecified"))
      (node (ref "U6") (pin "16") (pinfunction "P13_16") (pintype "unspecified"))
    )
    (net (code "16") (name "Button_Top") (class "Default")
      (node (ref "SW9") (pin "1") (pinfunction "1_1") (pintype "unspecified"))
      (node (ref "SW9") (pin "2") (pinfunction "2_2") (pintype "unspecified"))
      (node (ref "U6") (pin "17") (pinfunction "P14_17") (pintype "unspecified"))
    )
    (net (code "17") (name "Button_Voice") (class "Default")
      (node (ref "SW8") (pin "1") (pinfunction "1_1") (pintype "unspecified"))
      (node (ref "SW8") (pin "2") (pinfunction "2_2") (pintype "unspecified"))
      (node (ref "U6") (pin "20") (pinfunction "P17_20") (pintype "unspecified"))
    )
    (net (code "18") (name "CH343P_DTR") (class "Default")
      (node (ref "Q1") (pin "2") (pinfunction "E_2") (pintype "unspecified"))
      (node (ref "Q2") (pin "1") (pinfunction "B_1") (pintype "unspecified"))
      (node (ref "U3") (pin "12") (pinfunction "DTRTNOW_12") (pintype "unspecified"))
    )
    (net (code "19") (name "CH343P_RTS") (class "Default")
      (node (ref "Q1") (pin "1") (pinfunction "B_1") (pintype "unspecified"))
      (node (ref "Q2") (pin "2") (pinfunction "E_2") (pintype "unspecified"))
      (node (ref "U3") (pin "13") (pinfunction "RTS_13") (pintype "unspecified"))
    )
    (net (code "20") (name "CH343P_RX") (class "Default")
      (node (ref "U1") (pin "35") (pinfunction "TXD0_35") (pintype "unspecified"))
      (node (ref "U3") (pin "5") (pinfunction "RXD_5") (pintype "unspecified"))
    )
    (net (code "21") (name "CH343P_TX") (class "Default")
      (node (ref "U1") (pin "34") (pinfunction "RXD0_34") (pintype "unspecified"))
      (node (ref "U3") (pin "4") (pinfunction "TXD_4") (pintype "unspecified"))
    )
    (net (code "22") (name "DAC_DIN") (class "Default")
      (node (ref "U1") (pin "14") (pinfunction "IO12_14") (pintype "unspecified"))
    )
    (net (code "23") (name "ESP32_EN") (class "Default")
      (node (ref "C1") (pin "1") (pinfunction "1_1") (pintype "input"))
      (node (ref "Q1") (pin "3") (pinfunction "C_3") (pintype "unspecified"))
      (node (ref "R1") (pin "2") (pinfunction "2_2") (pintype "unspecified"))
      (node (ref "SW1") (pin "2") (pinfunction "2_2") (pintype "unspecified"))
      (node (ref "U1") (pin "3") (pinfunction "EN_3") (pintype "unspecified"))
    )
    (net (code "24") (name "ESP32_IO0") (class "Default")
      (node (ref "Q2") (pin "3") (pinfunction "C_3") (pintype "unspecified"))
      (node (ref "R2") (pin "1") (pinfunction "1_1") (pintype "unspecified"))
      (node (ref "SW2") (pin "1") (pinfunction "1_1") (pintype "unspecified"))
      (node (ref "U1") (pin "25") (pinfunction "IO0_25") (pintype "unspecified"))
    )
    (net (code "25") (name "EncoderA") (class "Default")
      (node (ref "R10") (pin "2") (pinfunction "2_2") (pintype "unspecified"))
      (node (ref "SW3") (pin "A") (pinfunction "A_A") (pintype "unspecified"))
      (node (ref "U1") (pin "5") (pinfunction "SENSOR_VN_5") (pintype "unspecified"))
    )
    (net (code "26") (name "EncoderB") (class "Default")
      (node (ref "R11") (pin "2") (pinfunction "2_2") (pintype "unspecified"))
      (node (ref "SW3") (pin "B") (pinfunction "B_B") (pintype "unspecified"))
      (node (ref "U1") (pin "4") (pinfunction "SENSOR_VP_4") (pintype "unspecified"))
    )
    (net (code "27") (name "GND") (class "Default")
      (node (ref "C1") (pin "2") (pinfunction "2_2") (pintype "input"))
      (node (ref "C10") (pin "1") (pinfunction "1_1") (pintype "unspecified"))
      (node (ref "C11") (pin "2") (pinfunction "2_2") (pintype "unspecified"))
      (node (ref "C12") (pin "2") (pinfunction "2_2") (pintype "unspecified"))
      (node (ref "C13") (pin "1") (pinfunction "1_1") (pintype "unspecified"))
      (node (ref "C14") (pin "1") (pinfunction "1_1") (pintype "unspecified"))
      (node (ref "C2") (pin "1") (pinfunction "1_1") (pintype "unspecified"))
      (node (ref "C3") (pin "2") (pinfunction "2_2") (pintype "unspecified"))
      (node (ref "C4") (pin "2") (pinfunction "2_2") (pintype "unspecified"))
      (node (ref "C5") (pin "2") (pinfunction "2_2") (pintype "unspecified"))
      (node (ref "C6") (pin "2") (pinfunction "2_2") (pintype "unspecified"))
      (node (ref "C7") (pin "2") (pinfunction "2_2") (pintype "unspecified"))
      (node (ref "C8") (pin "2") (pinfunction "2_2") (pintype "input"))
      (node (ref "C9") (pin "2") (pinfunction "2_2") (pintype "input"))
      (node (ref "OLED1") (pin "1") (pinfunction "1_1") (pintype "unspecified"))
      (node (ref "R3") (pin "1") (pinfunction "1_1") (pintype "unspecified"))
      (node (ref "R4") (pin "1") (pinfunction "1_1") (pintype "unspecified"))
      (node (ref "SW1") (pin "1") (pinfunction "1_1") (pintype "unspecified"))
      (node (ref "SW10") (pin "3") (pinfunction "3_3") (pintype "unspecified"))
      (node (ref "SW10") (pin "4") (pinfunction "4_4") (pintype "unspecified"))
      (node (ref "SW11") (pin "3") (pinfunction "3_3") (pintype "unspecified"))
      (node (ref "SW11") (pin "4") (pinfunction "4_4") (pintype "unspecified"))
      (node (ref "SW12") (pin "3") (pinfunction "3_3") (pintype "unspecified"))
      (node (ref "SW12") (pin "4") (pinfunction "4_4") (pintype "unspecified"))
      (node (ref "SW13") (pin "3") (pinfunction "3_3") (pintype "unspecified"))
      (node (ref "SW13") (pin "4") (pinfunction "4_4") (pintype "unspecified"))
      (node (ref "SW14") (pin "3") (pinfunction "3_3") (pintype "unspecified"))
      (node (ref "SW14") (pin "4") (pinfunction "4_4") (pintype "unspecified"))
      (node (ref "SW15") (pin "3") (pinfunction "3_3") (pintype "unspecified"))
      (node (ref "SW15") (pin "4") (pinfunction "4_4") (pintype "unspecified"))
      (node (ref "SW16") (pin "3") (pinfunction "3_3") (pintype "unspecified"))
      (node (ref "SW16") (pin "4") (pinfunction "4_4") (pintype "unspecified"))
      (node (ref "SW17") (pin "3") (pinfunction "3_3") (pintype "unspecified"))
      (node (ref "SW17") (pin "4") (pinfunction "4_4") (pintype "unspecified"))
      (node (ref "SW18") (pin "3") (pinfunction "3_3") (pintype "unspecified"))
      (node (ref "SW18") (pin "4") (pinfunction "4_4") (pintype "unspecified"))
      (node (ref "SW19") (pin "3") (pinfunction "3_3") (pintype "unspecified"))
      (node (ref "SW19") (pin "4") (pinfunction "4_4") (pintype "unspecified"))
      (node (ref "SW2") (pin "2") (pinfunction "2_2") (pintype "unspecified"))
      (node (ref "SW3") (pin "6") (pinfunction "6_6") (pintype "unspecified"))
      (node (ref "SW3") (pin "7") (pinfunction "7_7") (pintype "unspecified"))
      (node (ref "SW3") (pin "C") (pinfunction "C_C") (pintype "unspecified"))
      (node (ref "SW3") (pin "E") (pinfunction "E_E") (pintype "unspecified"))
      (node (ref "SW4") (pin "3") (pinfunction "3_3") (pintype "unspecified"))
      (node (ref "SW4") (pin "4") (pinfunction "4_4") (pintype "unspecified"))
      (node (ref "SW5") (pin "3") (pinfunction "3_3") (pintype "unspecified"))
      (node (ref "SW5") (pin "4") (pinfunction "4_4") (pintype "unspecified"))
      (node (ref "SW6") (pin "3") (pinfunction "3_3") (pintype "unspecified"))
      (node (ref "SW6") (pin "4") (pinfunction "4_4") (pintype "unspecified"))
      (node (ref "SW7") (pin "3") (pinfunction "3_3") (pintype "unspecified"))
      (node (ref "SW7") (pin "4") (pinfunction "4_4") (pintype "unspecified"))
      (node (ref "SW8") (pin "3") (pinfunction "3_3") (pintype "unspecified"))
      (node (ref "SW8") (pin "4") (pinfunction "4_4") (pintype "unspecified"))
      (node (ref "SW9") (pin "3") (pinfunction "3_3") (pintype "unspecified"))
      (node (ref "SW9") (pin "4") (pinfunction "4_4") (pintype "unspecified"))
      (node (ref "U1") (pin "1") (pinfunction "GND_1") (pintype "unspecified"))
      (node (ref "U1") (pin "15") (pinfunction "GND_15") (pintype "unspecified"))
      (node (ref "U1") (pin "38") (pinfunction "GND_38") (pintype "unspecified"))
      (node (ref "U1") (pin "39") (pinfunction "GND_39") (pintype "unspecified"))
      (node (ref "U2") (pin "10") (pinfunction "GND_10") (pintype "unspecified"))
      (node (ref "U2") (pin "16") (pinfunction "GND_16") (pintype "unspecified"))
      (node (ref "U2") (pin "2") (pinfunction "GND_2") (pintype "unspecified"))
      (node (ref "U2") (pin "7") (pinfunction "GND_7") (pintype "unspecified"))
      (node (ref "U3") (pin "17") (pinfunction "EP_17") (pintype "unspecified"))
      (node (ref "U3") (pin "2") (pinfunction "GND_2") (pintype "unspecified"))
      (node (ref "U4") (pin "2") (pinfunction "LR_2") (pintype "unspecified"))
      (node (ref "U4") (pin "3") (pinfunction "GND_3") (pintype "unspecified"))
      (node (ref "U5") (pin "11") (pinfunction "GND_11") (pintype "unspecified"))
      (node (ref "U5") (pin "15") (pinfunction "GND_15") (pintype "unspecified"))
      (node (ref "U5") (pin "17") (pinfunction "EP_17") (pintype "unspecified"))
      (node (ref "U5") (pin "2") (pinfunction "GAIN_SLOT_2") (pintype "unspecified"))
      (node (ref "U5") (pin "3") (pinfunction "GND_3") (pintype "unspecified"))
      (node (ref "U6") (pin "12") (pinfunction "GND_12") (pintype "unspecified"))
      (node (ref "U6") (pin "2") (pinfunction "A1_2") (pintype "unspecified"))
      (node (ref "U6") (pin "21") (pinfunction "A0_21") (pintype "unspecified"))
      (node (ref "U6") (pin "3") (pinfunction "A2_3") (pintype "unspecified"))
      (node (ref "U7") (pin "12") (pinfunction "GND_12") (pintype "unspecified"))
      (node (ref "U7") (pin "2") (pinfunction "A1_2") (pintype "unspecified"))
      (node (ref "U7") (pin "3") (pinfunction "A2_3") (pintype "unspecified"))
      (node (ref "USBC1") (pin "1") (pinfunction "EH_1") (pintype "unspecified"))
      (node (ref "USBC1") (pin "2") (pinfunction "EH_2") (pintype "unspecified"))
      (node (ref "USBC1") (pin "3") (pinfunction "EH_3") (pintype "unspecified"))
      (node (ref "USBC1") (pin "4") (pinfunction "EH_4") (pintype "unspecified"))
      (node (ref "USBC1") (pin "A1B12") (pinfunction "GND_A1B12") (pintype "unspecified"))
      (node (ref "USBC1") (pin "B1A12") (pinfunction "GND_B1A12") (pintype "unspecified"))
    )
    (net (code "28") (name "IO_INT") (class "Default")
      (node (ref "R8") (pin "2") (pinfunction "2_2") (pintype "unspecified"))
      (node (ref "R9") (pin "2") (pinfunction "2_2") (pintype "unspecified"))
      (node (ref "U1") (pin "27") (pinfunction "IO16_27") (pintype "unspecified"))
      (node (ref "U6") (pin "1") (pinfunction "INT#_1") (pintype "unspecified"))
      (node (ref "U7") (pin "1") (pinfunction "INT#_1") (pintype "unspecified"))
    )
    (net (code "29") (name "Knob_PushDown") (class "Default")
      (node (ref "SW3") (pin "D") (pinfunction "D_D") (pintype "unspecified"))
      (node (ref "U7") (pin "4") (pinfunction "P00_4") (pintype "unspecified"))
    )
    (net (code "30") (name "LoRa_BUSY") (class "Default")
      (node (ref "U1") (pin "6") (pinfunction "IO34_6") (pintype "unspecified"))
      (node (ref "U2") (pin "12") (pinfunction "BUSY_12") (pintype "unspecified"))
    )
    (net (code "31") (name "LoRa_DIO1") (class "Default")
      (node (ref "U1") (pin "7") (pinfunction "IO35_7") (pintype "unspecified"))
      (node (ref "U2") (pin "13") (pinfunction "DIO1_13") (pintype "unspecified"))
    )
    (net (code "32") (name "LoRa_RST") (class "Default")
      (node (ref "U1") (pin "13") (pinfunction "IO14_13") (pintype "unspecified"))
      (node (ref "U2") (pin "11") (pinfunction "NRESET_11") (pintype "unspecified"))
    )
    (net (code "33") (name "LoRa_RX_EN") (class "Default")
      (node (ref "U1") (pin "26") (pinfunction "IO4_26") (pintype "unspecified"))
      (node (ref "U2") (pin "8") (pinfunction "RX_EN_8") (pintype "unspecified"))
    )
    (net (code "34") (name "LoRa_SPI_SS") (class "Default")
      (node (ref "R7") (pin "2") (pinfunction "2_2") (pintype "unspecified"))
      (node (ref "U1") (pin "29") (pinfunction "IO5_29") (pintype "unspecified"))
      (node (ref "U2") (pin "6") (pinfunction "NSS_CTS_6") (pintype "unspecified"))
    )
    (net (code "35") (name "LoRa_TX_EN") (class "Default")
      (node (ref "U1") (pin "16") (pinfunction "IO13_16") (pintype "unspecified"))
      (node (ref "U2") (pin "9") (pinfunction "TX_EN_9") (pintype "unspecified"))
    )
    (net (code "36") (name "MicSCK") (class "Default")
      (node (ref "U1") (pin "8") (pinfunction "IO32_8") (pintype "unspecified"))
      (node (ref "U4") (pin "4") (pinfunction "SCK_4") (pintype "unspecified"))
    )
    (net (code "37") (name "MicSD") (class "Default")
      (node (ref "U1") (pin "9") (pinfunction "IO33_9") (pintype "unspecified"))
      (node (ref "U4") (pin "6") (pinfunction "SD_6") (pintype "unspecified"))
    )
    (net (code "38") (name "MicWS") (class "Default")
      (node (ref "U1") (pin "10") (pinfunction "IO25_10") (pintype "unspecified"))
      (node (ref "U4") (pin "1") (pinfunction "WS_1") (pintype "unspecified"))
    )
    (net (code "39") (name "Net-(C2-Pad2)") (class "Default")
      (node (ref "C2") (pin "2") (pinfunction "2_2") (pintype "unspecified"))
      (node (ref "C6") (pin "1") (pinfunction "1_1") (pintype "unspecified"))
    )
    (net (code "40") (name "Net-(U3-UD+)") (class "Default")
      (node (ref "U3") (pin "7") (pinfunction "UD+_7") (pintype "unspecified"))
      (node (ref "USBC1") (pin "A6") (pinfunction "DP1_A6") (pintype "unspecified"))
      (node (ref "USBC1") (pin "B6") (pinfunction "DP2_B6") (pintype "unspecified"))
    )
    (net (code "41") (name "Net-(U3-UD-)") (class "Default")
      (node (ref "U3") (pin "8") (pinfunction "UD-_8") (pintype "unspecified"))
      (node (ref "USBC1") (pin "A7") (pinfunction "DN1_A7") (pintype "unspecified"))
      (node (ref "USBC1") (pin "B7") (pinfunction "DN2_B7") (pintype "unspecified"))
    )
    (net (code "42") (name "Net-(U3-V3)") (class "Default")
      (node (ref "C4") (pin "1") (pinfunction "1_1") (pintype "unspecified"))
      (node (ref "U3") (pin "6") (pinfunction "V3_6") (pintype "unspecified"))
    )
    (net (code "43") (name "Net-(USBC1-CC1)") (class "Default")
      (node (ref "R3") (pin "2") (pinfunction "2_2") (pintype "unspecified"))
      (node (ref "USBC1") (pin "A5") (pinfunction "CC1_A5") (pintype "unspecified"))
    )
    (net (code "44") (name "Net-(USBC1-CC2)") (class "Default")
      (node (ref "R4") (pin "2") (pinfunction "2_2") (pintype "unspecified"))
      (node (ref "USBC1") (pin "B5") (pinfunction "CC2_B5") (pintype "unspecified"))
    )
    (net (code "45") (name "SCK_MISO") (class "Default")
      (node (ref "U1") (pin "37") (pinfunction "IO23_37") (pintype "unspecified"))
    )
    (net (code "46") (name "SCK_MOSI") (class "Default")
      (node (ref "U1") (pin "31") (pinfunction "IO19_31") (pintype "unspecified"))
    )
    (net (code "47") (name "SCL") (class "Default")
      (node (ref "OLED1") (pin "3") (pinfunction "3_3") (pintype "unspecified"))
      (node (ref "R5") (pin "1") (pinfunction "1_1") (pintype "input"))
      (node (ref "U1") (pin "36") (pinfunction "IO22_36") (pintype "unspecified"))
      (node (ref "U6") (pin "22") (pinfunction "SCL_22") (pintype "unspecified"))
      (node (ref "U7") (pin "22") (pinfunction "SCL_22") (pintype "unspecified"))
    )
    (net (code "48") (name "SDA") (class "Default")
      (node (ref "OLED1") (pin "4") (pinfunction "4_4") (pintype "unspecified"))
      (node (ref "R6") (pin "1") (pinfunction "1_1") (pintype "input"))
      (node (ref "U1") (pin "33") (pinfunction "IO21_33") (pintype "unspecified"))
      (node (ref "U6") (pin "23") (pinfunction "SDA_23") (pintype "unspecified"))
      (node (ref "U7") (pin "23") (pinfunction "SDA_23") (pintype "unspecified"))
    )
    (net (code "49") (name "SPI_MISO") (class "Default")
      (node (ref "U2") (pin "3") (pinfunction "MISO_TX_3") (pintype "unspecified"))
    )
    (net (code "50") (name "SPI_MOSI") (class "Default")
      (node (ref "U2") (pin "4") (pinfunction "MOSI_RX_4") (pintype "unspecified"))
    )
    (net (code "51") (name "SPI_SCK") (class "Default")
      (node (ref "U1") (pin "30") (pinfunction "IO18_30") (pintype "unspecified"))
      (node (ref "U2") (pin "5") (pinfunction "SCK_RTSN_5") (pintype "unspecified"))
    )
    (net (code "52") (name "Sound_BCLK") (class "Default")
      (node (ref "U1") (pin "12") (pinfunction "IO27_12") (pintype "unspecified"))
      (node (ref "U5") (pin "16") (pinfunction "BCLK_16") (pintype "unspecified"))
    )
    (net (code "53") (name "Sound_DIN") (class "Default")
      (node (ref "U1") (pin "28") (pinfunction "IO17_28") (pintype "unspecified"))
      (node (ref "U5") (pin "1") (pinfunction "DIN_1") (pintype "unspecified"))
    )
    (net (code "54") (name "Sound_LRC") (class "Default")
      (node (ref "U1") (pin "11") (pinfunction "IO26_11") (pintype "unspecified"))
      (node (ref "U5") (pin "14") (pinfunction "LRCLK_14") (pintype "unspecified"))
    )
    (net (code "55") (name "Speaker+") (class "Default")
      (node (ref "U5") (pin "9") (pinfunction "OUTP_9") (pintype "unspecified"))
    )
    (net (code "56") (name "Speaker-") (class "Default")
      (node (ref "U5") (pin "10") (pinfunction "OUTN_10") (pintype "unspecified"))
    )
    (net (code "57") (name "VBAT") (class "Default")
      (node (ref "C12") (pin "1") (pinfunction "1_1") (pintype "unspecified"))
      (node (ref "C13") (pin "2") (pinfunction "2_2") (pintype "unspecified"))
      (node (ref "U5") (pin "7") (pinfunction "VDD_7") (pintype "unspecified"))
      (node (ref "U5") (pin "8") (pinfunction "VDD_8") (pintype "unspecified"))
    )
    (net (code "58") (name "VBUS") (class "Default")
      (node (ref "C3") (pin "1") (pinfunction "1_1") (pintype "unspecified"))
      (node (ref "U3") (pin "3") (pinfunction "VDD5_3") (pintype "unspecified"))
      (node (ref "U3") (pin "9") (pinfunction "VBUS_9") (pintype "unspecified"))
      (node (ref "USBC1") (pin "A4B9") (pinfunction "VBUS_A4B9") (pintype "unspecified"))
      (node (ref "USBC1") (pin "B4A9") (pinfunction "VBUS_B4A9") (pintype "unspecified"))
    )
    (net (code "59") (name "unconnected-(U1-IO2-Pad24)") (class "Default")
      (node (ref "U1") (pin "24") (pinfunction "IO2_24") (pintype "unspecified"))
    )
    (net (code "60") (name "unconnected-(U1-IO15-Pad23)") (class "Default")
      (node (ref "U1") (pin "23") (pinfunction "IO15_23") (pintype "unspecified"))
    )
    (net (code "61") (name "unconnected-(U1-NC-Pad17)") (class "Default")
      (node (ref "U1") (pin "17") (pinfunction "NC_17") (pintype "unspecified"))
    )
    (net (code "62") (name "unconnected-(U1-NC-Pad18)") (class "Default")
      (node (ref "U1") (pin "18") (pinfunction "NC_18") (pintype "unspecified"))
    )
    (net (code "63") (name "unconnected-(U1-NC-Pad19)") (class "Default")
      (node (ref "U1") (pin "19") (pinfunction "NC_19") (pintype "unspecified"))
    )
    (net (code "64") (name "unconnected-(U1-NC-Pad20)") (class "Default")
      (node (ref "U1") (pin "20") (pinfunction "NC_20") (pintype "unspecified"))
    )
    (net (code "65") (name "unconnected-(U1-NC-Pad21)") (class "Default")
      (node (ref "U1") (pin "21") (pinfunction "NC_21") (pintype "unspecified"))
    )
    (net (code "66") (name "unconnected-(U1-NC-Pad22)") (class "Default")
      (node (ref "U1") (pin "22") (pinfunction "NC_22") (pintype "unspecified"))
    )
    (net (code "67") (name "unconnected-(U1-NC-Pad32)") (class "Default")
      (node (ref "U1") (pin "32") (pinfunction "NC_32") (pintype "unspecified"))
    )
    (net (code "68") (name "unconnected-(U2-DIO2-Pad14)") (class "Default")
      (node (ref "U2") (pin "14") (pinfunction "DIO2_14") (pintype "unspecified"))
    )
    (net (code "69") (name "unconnected-(U2-DIO3-Pad15)") (class "Default")
      (node (ref "U2") (pin "15") (pinfunction "DIO3_15") (pintype "unspecified"))
    )
    (net (code "70") (name "unconnected-(U3-ACT#-Pad10)") (class "Default")
      (node (ref "U3") (pin "10") (pinfunction "ACT#_10") (pintype "unspecified"))
    )
    (net (code "71") (name "unconnected-(U3-CTS-Pad15)") (class "Default")
      (node (ref "U3") (pin "15") (pinfunction "CTS_15") (pintype "unspecified"))
    )
    (net (code "72") (name "unconnected-(U3-DCD-Pad11)") (class "Default")
      (node (ref "U3") (pin "11") (pinfunction "DCD_11") (pintype "unspecified"))
    )
    (net (code "73") (name "unconnected-(U3-DSR-Pad14)") (class "Default")
      (node (ref "U3") (pin "14") (pinfunction "DSR_14") (pintype "unspecified"))
    )
    (net (code "74") (name "unconnected-(U3-RI-Pad16)") (class "Default")
      (node (ref "U3") (pin "16") (pinfunction "RI_16") (pintype "unspecified"))
    )
    (net (code "75") (name "unconnected-(U5-N.C.-Pad5)") (class "Default")
      (node (ref "U5") (pin "5") (pinfunction "N.C._5") (pintype "unspecified"))
    )
    (net (code "76") (name "unconnected-(U5-N.C.-Pad6)") (class "Default")
      (node (ref "U5") (pin "6") (pinfunction "N.C._6") (pintype "unspecified"))
    )
    (net (code "77") (name "unconnected-(U5-N.C.-Pad12)") (class "Default")
      (node (ref "U5") (pin "12") (pinfunction "N.C._12") (pintype "unspecified"))
    )
    (net (code "78") (name "unconnected-(U5-N.C.-Pad13)") (class "Default")
      (node (ref "U5") (pin "13") (pinfunction "N.C._13") (pintype "unspecified"))
    )
    (net (code "79") (name "unconnected-(U7-P01-Pad5)") (class "Default")
      (node (ref "U7") (pin "5") (pinfunction "P01_5") (pintype "unspecified"))
    )
    (net (code "80") (name "unconnected-(U7-P02-Pad6)") (class "Default")
      (node (ref "U7") (pin "6") (pinfunction "P02_6") (pintype "unspecified"))
    )
    (net (code "81") (name "unconnected-(U7-P03-Pad7)") (class "Default")
      (node (ref "U7") (pin "7") (pinfunction "P03_7") (pintype "unspecified"))
    )
    (net (code "82") (name "unconnected-(U7-P04-Pad8)") (class "Default")
      (node (ref "U7") (pin "8") (pinfunction "P04_8") (pintype "unspecified"))
    )
    (net (code "83") (name "unconnected-(U7-P05-Pad9)") (class "Default")
      (node (ref "U7") (pin "9") (pinfunction "P05_9") (pintype "unspecified"))
    )
    (net (code "84") (name "unconnected-(U7-P06-Pad10)") (class "Default")
      (node (ref "U7") (pin "10") (pinfunction "P06_10") (pintype "unspecified"))
    )
    (net (code "85") (name "unconnected-(U7-P07-Pad11)") (class "Default")
      (node (ref "U7") (pin "11") (pinfunction "P07_11") (pintype "unspecified"))
    )
    (net (code "86") (name "unconnected-(U7-P10-Pad13)") (class "Default")
      (node (ref "U7") (pin "13") (pinfunction "P10_13") (pintype "unspecified"))
    )
    (net (code "87") (name "unconnected-(U7-P11-Pad14)") (class "Default")
      (node (ref "U7") (pin "14") (pinfunction "P11_14") (pintype "unspecified"))
    )
    (net (code "88") (name "unconnected-(U7-P12-Pad15)") (class "Default")
      (node (ref "U7") (pin "15") (pinfunction "P12_15") (pintype "unspecified"))
    )
    (net (code "89") (name "unconnected-(U7-P13-Pad16)") (class "Default")
      (node (ref "U7") (pin "16") (pinfunction "P13_16") (pintype "unspecified"))
    )
    (net (code "90") (name "unconnected-(U7-P14-Pad17)") (class "Default")
      (node (ref "U7") (pin "17") (pinfunction "P14_17") (pintype "unspecified"))
    )
    (net (code "91") (name "unconnected-(U7-P15-Pad18)") (class "Default")
      (node (ref "U7") (pin "18") (pinfunction "P15_18") (pintype "unspecified"))
    )
    (net (code "92") (name "unconnected-(U7-P16-Pad19)") (class "Default")
      (node (ref "U7") (pin "19") (pinfunction "P16_19") (pintype "unspecified"))
    )
    (net (code "93") (name "unconnected-(U7-P17-Pad20)") (class "Default")
      (node (ref "U7") (pin "20") (pinfunction "P17_20") (pintype "unspecified"))
    )
    (net (code "94") (name "unconnected-(USBC1-SBU1-PadA8)") (class "Default")
      (node (ref "USBC1") (pin "A8") (pinfunction "SBU1_A8") (pintype "unspecified"))
    )
    (net (code "95") (name "unconnected-(USBC1-SBU2-PadB8)") (class "Default")
      (node (ref "USBC1") (pin "B8") (pinfunction "SBU2_B8") (pintype "unspecified"))
    )
  )
)
